# pcb.net
KiCad netlist of a schematic drawn in EAGLE
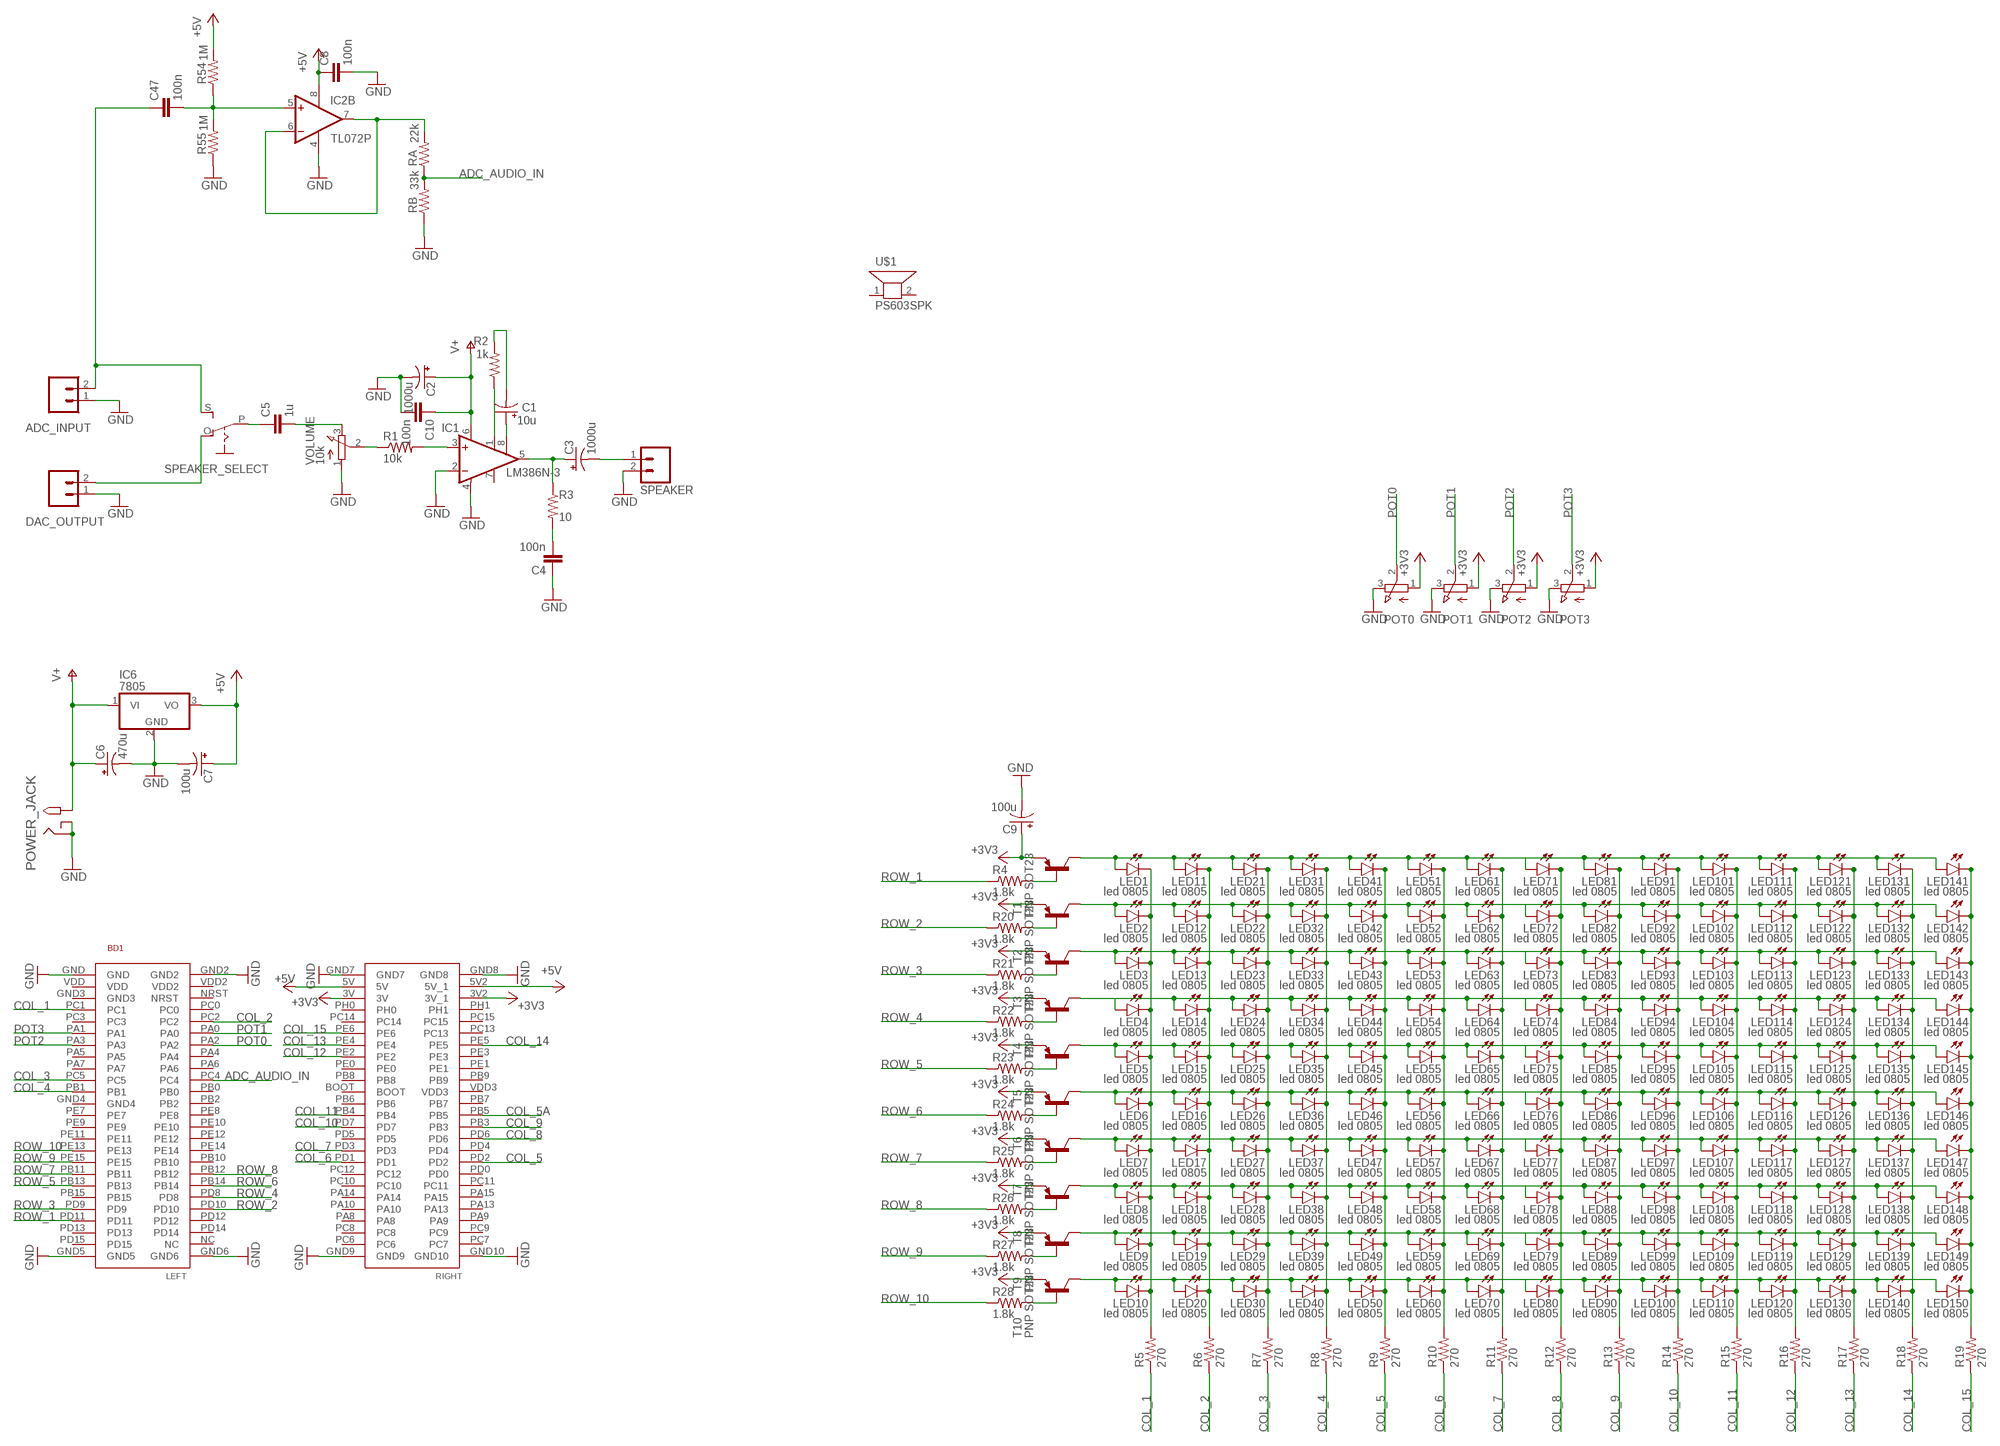
[diagram p0: schematic, sheet 1]

(export (version "E")
  (design (tool "Eeschema 10.0.6"))
  (components
    (comp (ref "ADC_INPUT")
      (value "M02")
      (footprint "eagle-import:02P")
      (libsource (lib "eagle-import") (part "M02"))
    )
    (comp (ref "BD1")
      (value "STM32F4-DISCOVERY")
      (footprint "eagle-import:STM32F407VG")
      (libsource (lib "eagle-import") (part "STM32F4-DISCOVERY"))
    )
    (comp (ref "C1")
      (value "10u")
      (footprint "eagle-import:E5-6")
      (libsource (lib "eagle-import") (part "CPOL-USE5-6"))
    )
    (comp (ref "C2")
      (value "1000u")
      (footprint "eagle-import:E5-13")
      (libsource (lib "eagle-import") (part "CPOL-USE5-13"))
    )
    (comp (ref "C3")
      (value "1000u")
      (footprint "eagle-import:E5-13")
      (libsource (lib "eagle-import") (part "CPOL-USE5-13"))
    )
    (comp (ref "C4")
      (value "100n")
      (footprint "eagle-import:C5B3.5")
      (libsource (lib "eagle-import") (part "C5/3.5"))
    )
    (comp (ref "C5")
      (value "1u")
      (footprint "eagle-import:C050-035X075")
      (libsource (lib "eagle-import") (part "rcl_334_C-EU050-035X075"))
    )
    (comp (ref "C6")
      (value "470u")
      (footprint "eagle-import:E5-6")
      (libsource (lib "eagle-import") (part "CPOL-USE5-6"))
    )
    (comp (ref "C7")
      (value "100u")
      (footprint "eagle-import:E5-6")
      (libsource (lib "eagle-import") (part "CPOL-USE5-6"))
    )
    (comp (ref "C8")
      (value "100n")
      (footprint "eagle-import:C0805")
      (libsource (lib "eagle-import") (part "C-EUC0805"))
    )
    (comp (ref "C9")
      (value "100u")
      (footprint "eagle-import:E5-6")
      (libsource (lib "eagle-import") (part "CPOL-USE5-6"))
    )
    (comp (ref "C10")
      (value "100n")
      (footprint "eagle-import:C0805")
      (libsource (lib "eagle-import") (part "C-EUC0805"))
    )
    (comp (ref "C47")
      (value "100n")
      (footprint "eagle-import:C5B3.5")
      (libsource (lib "eagle-import") (part "C5/3.5"))
    )
    (comp (ref "DAC_OUTPUT")
      (value "M02")
      (footprint "eagle-import:02P")
      (libsource (lib "eagle-import") (part "M02"))
    )
    (comp (ref "IC1")
      (value "LM386N-3")
      (footprint "eagle-import:DIL08")
      (libsource (lib "eagle-import") (part "LM386?-N3"))
    )
    (comp (ref "IC2")
      (value "TL072P")
      (footprint "eagle-import:DIL08")
      (libsource (lib "eagle-import") (part "TL072P"))
    )
    (comp (ref "IC6")
      (value "7805")
      (footprint "eagle-import:TO220H")
      (libsource (lib "eagle-import") (part "78T05"))
    )
    (comp (ref "LED1")
      (value "led 0805")
      (footprint "eagle-import:CHIPLED_0805")
      (libsource (lib "eagle-import") (part "LEDCHIPLED_0805"))
    )
    (comp (ref "LED2")
      (value "led 0805")
      (footprint "eagle-import:CHIPLED_0805")
      (libsource (lib "eagle-import") (part "LEDCHIPLED_0805"))
    )
    (comp (ref "LED3")
      (value "led 0805")
      (footprint "eagle-import:CHIPLED_0805")
      (libsource (lib "eagle-import") (part "LEDCHIPLED_0805"))
    )
    (comp (ref "LED4")
      (value "led 0805")
      (footprint "eagle-import:CHIPLED_0805")
      (libsource (lib "eagle-import") (part "LEDCHIPLED_0805"))
    )
    (comp (ref "LED5")
      (value "led 0805")
      (footprint "eagle-import:CHIPLED_0805")
      (libsource (lib "eagle-import") (part "LEDCHIPLED_0805"))
    )
    (comp (ref "LED6")
      (value "led 0805")
      (footprint "eagle-import:CHIPLED_0805")
      (libsource (lib "eagle-import") (part "LEDCHIPLED_0805"))
    )
    (comp (ref "LED7")
      (value "led 0805")
      (footprint "eagle-import:CHIPLED_0805")
      (libsource (lib "eagle-import") (part "LEDCHIPLED_0805"))
    )
    (comp (ref "LED8")
      (value "led 0805")
      (footprint "eagle-import:CHIPLED_0805")
      (libsource (lib "eagle-import") (part "LEDCHIPLED_0805"))
    )
    (comp (ref "LED9")
      (value "led 0805")
      (footprint "eagle-import:CHIPLED_0805")
      (libsource (lib "eagle-import") (part "LEDCHIPLED_0805"))
    )
    (comp (ref "LED10")
      (value "led 0805")
      (footprint "eagle-import:CHIPLED_0805")
      (libsource (lib "eagle-import") (part "LEDCHIPLED_0805"))
    )
    (comp (ref "LED11")
      (value "led 0805")
      (footprint "eagle-import:CHIPLED_0805")
      (libsource (lib "eagle-import") (part "LEDCHIPLED_0805"))
    )
    (comp (ref "LED12")
      (value "led 0805")
      (footprint "eagle-import:CHIPLED_0805")
      (libsource (lib "eagle-import") (part "LEDCHIPLED_0805"))
    )
    (comp (ref "LED13")
      (value "led 0805")
      (footprint "eagle-import:CHIPLED_0805")
      (libsource (lib "eagle-import") (part "LEDCHIPLED_0805"))
    )
    (comp (ref "LED14")
      (value "led 0805")
      (footprint "eagle-import:CHIPLED_0805")
      (libsource (lib "eagle-import") (part "LEDCHIPLED_0805"))
    )
    (comp (ref "LED15")
      (value "led 0805")
      (footprint "eagle-import:CHIPLED_0805")
      (libsource (lib "eagle-import") (part "LEDCHIPLED_0805"))
    )
    (comp (ref "LED16")
      (value "led 0805")
      (footprint "eagle-import:CHIPLED_0805")
      (libsource (lib "eagle-import") (part "LEDCHIPLED_0805"))
    )
    (comp (ref "LED17")
      (value "led 0805")
      (footprint "eagle-import:CHIPLED_0805")
      (libsource (lib "eagle-import") (part "LEDCHIPLED_0805"))
    )
    (comp (ref "LED18")
      (value "led 0805")
      (footprint "eagle-import:CHIPLED_0805")
      (libsource (lib "eagle-import") (part "LEDCHIPLED_0805"))
    )
    (comp (ref "LED19")
      (value "led 0805")
      (footprint "eagle-import:CHIPLED_0805")
      (libsource (lib "eagle-import") (part "LEDCHIPLED_0805"))
    )
    (comp (ref "LED20")
      (value "led 0805")
      (footprint "eagle-import:CHIPLED_0805")
      (libsource (lib "eagle-import") (part "LEDCHIPLED_0805"))
    )
    (comp (ref "LED21")
      (value "led 0805")
      (footprint "eagle-import:CHIPLED_0805")
      (libsource (lib "eagle-import") (part "LEDCHIPLED_0805"))
    )
    (comp (ref "LED22")
      (value "led 0805")
      (footprint "eagle-import:CHIPLED_0805")
      (libsource (lib "eagle-import") (part "LEDCHIPLED_0805"))
    )
    (comp (ref "LED23")
      (value "led 0805")
      (footprint "eagle-import:CHIPLED_0805")
      (libsource (lib "eagle-import") (part "LEDCHIPLED_0805"))
    )
    (comp (ref "LED24")
      (value "led 0805")
      (footprint "eagle-import:CHIPLED_0805")
      (libsource (lib "eagle-import") (part "LEDCHIPLED_0805"))
    )
    (comp (ref "LED25")
      (value "led 0805")
      (footprint "eagle-import:CHIPLED_0805")
      (libsource (lib "eagle-import") (part "LEDCHIPLED_0805"))
    )
    (comp (ref "LED26")
      (value "led 0805")
      (footprint "eagle-import:CHIPLED_0805")
      (libsource (lib "eagle-import") (part "LEDCHIPLED_0805"))
    )
    (comp (ref "LED27")
      (value "led 0805")
      (footprint "eagle-import:CHIPLED_0805")
      (libsource (lib "eagle-import") (part "LEDCHIPLED_0805"))
    )
    (comp (ref "LED28")
      (value "led 0805")
      (footprint "eagle-import:CHIPLED_0805")
      (libsource (lib "eagle-import") (part "LEDCHIPLED_0805"))
    )
    (comp (ref "LED29")
      (value "led 0805")
      (footprint "eagle-import:CHIPLED_0805")
      (libsource (lib "eagle-import") (part "LEDCHIPLED_0805"))
    )
    (comp (ref "LED30")
      (value "led 0805")
      (footprint "eagle-import:CHIPLED_0805")
      (libsource (lib "eagle-import") (part "LEDCHIPLED_0805"))
    )
    (comp (ref "LED31")
      (value "led 0805")
      (footprint "eagle-import:CHIPLED_0805")
      (libsource (lib "eagle-import") (part "LEDCHIPLED_0805"))
    )
    (comp (ref "LED32")
      (value "led 0805")
      (footprint "eagle-import:CHIPLED_0805")
      (libsource (lib "eagle-import") (part "LEDCHIPLED_0805"))
    )
    (comp (ref "LED33")
      (value "led 0805")
      (footprint "eagle-import:CHIPLED_0805")
      (libsource (lib "eagle-import") (part "LEDCHIPLED_0805"))
    )
    (comp (ref "LED34")
      (value "led 0805")
      (footprint "eagle-import:CHIPLED_0805")
      (libsource (lib "eagle-import") (part "LEDCHIPLED_0805"))
    )
    (comp (ref "LED35")
      (value "led 0805")
      (footprint "eagle-import:CHIPLED_0805")
      (libsource (lib "eagle-import") (part "LEDCHIPLED_0805"))
    )
    (comp (ref "LED36")
      (value "led 0805")
      (footprint "eagle-import:CHIPLED_0805")
      (libsource (lib "eagle-import") (part "LEDCHIPLED_0805"))
    )
    (comp (ref "LED37")
      (value "led 0805")
      (footprint "eagle-import:CHIPLED_0805")
      (libsource (lib "eagle-import") (part "LEDCHIPLED_0805"))
    )
    (comp (ref "LED38")
      (value "led 0805")
      (footprint "eagle-import:CHIPLED_0805")
      (libsource (lib "eagle-import") (part "LEDCHIPLED_0805"))
    )
    (comp (ref "LED39")
      (value "led 0805")
      (footprint "eagle-import:CHIPLED_0805")
      (libsource (lib "eagle-import") (part "LEDCHIPLED_0805"))
    )
    (comp (ref "LED40")
      (value "led 0805")
      (footprint "eagle-import:CHIPLED_0805")
      (libsource (lib "eagle-import") (part "LEDCHIPLED_0805"))
    )
    (comp (ref "LED41")
      (value "led 0805")
      (footprint "eagle-import:CHIPLED_0805")
      (libsource (lib "eagle-import") (part "LEDCHIPLED_0805"))
    )
    (comp (ref "LED42")
      (value "led 0805")
      (footprint "eagle-import:CHIPLED_0805")
      (libsource (lib "eagle-import") (part "LEDCHIPLED_0805"))
    )
    (comp (ref "LED43")
      (value "led 0805")
      (footprint "eagle-import:CHIPLED_0805")
      (libsource (lib "eagle-import") (part "LEDCHIPLED_0805"))
    )
    (comp (ref "LED44")
      (value "led 0805")
      (footprint "eagle-import:CHIPLED_0805")
      (libsource (lib "eagle-import") (part "LEDCHIPLED_0805"))
    )
    (comp (ref "LED45")
      (value "led 0805")
      (footprint "eagle-import:CHIPLED_0805")
      (libsource (lib "eagle-import") (part "LEDCHIPLED_0805"))
    )
    (comp (ref "LED46")
      (value "led 0805")
      (footprint "eagle-import:CHIPLED_0805")
      (libsource (lib "eagle-import") (part "LEDCHIPLED_0805"))
    )
    (comp (ref "LED47")
      (value "led 0805")
      (footprint "eagle-import:CHIPLED_0805")
      (libsource (lib "eagle-import") (part "LEDCHIPLED_0805"))
    )
    (comp (ref "LED48")
      (value "led 0805")
      (footprint "eagle-import:CHIPLED_0805")
      (libsource (lib "eagle-import") (part "LEDCHIPLED_0805"))
    )
    (comp (ref "LED49")
      (value "led 0805")
      (footprint "eagle-import:CHIPLED_0805")
      (libsource (lib "eagle-import") (part "LEDCHIPLED_0805"))
    )
    (comp (ref "LED50")
      (value "led 0805")
      (footprint "eagle-import:CHIPLED_0805")
      (libsource (lib "eagle-import") (part "LEDCHIPLED_0805"))
    )
    (comp (ref "LED51")
      (value "led 0805")
      (footprint "eagle-import:CHIPLED_0805")
      (libsource (lib "eagle-import") (part "LEDCHIPLED_0805"))
    )
    (comp (ref "LED52")
      (value "led 0805")
      (footprint "eagle-import:CHIPLED_0805")
      (libsource (lib "eagle-import") (part "LEDCHIPLED_0805"))
    )
    (comp (ref "LED53")
      (value "led 0805")
      (footprint "eagle-import:CHIPLED_0805")
      (libsource (lib "eagle-import") (part "LEDCHIPLED_0805"))
    )
    (comp (ref "LED54")
      (value "led 0805")
      (footprint "eagle-import:CHIPLED_0805")
      (libsource (lib "eagle-import") (part "LEDCHIPLED_0805"))
    )
    (comp (ref "LED55")
      (value "led 0805")
      (footprint "eagle-import:CHIPLED_0805")
      (libsource (lib "eagle-import") (part "LEDCHIPLED_0805"))
    )
    (comp (ref "LED56")
      (value "led 0805")
      (footprint "eagle-import:CHIPLED_0805")
      (libsource (lib "eagle-import") (part "LEDCHIPLED_0805"))
    )
    (comp (ref "LED57")
      (value "led 0805")
      (footprint "eagle-import:CHIPLED_0805")
      (libsource (lib "eagle-import") (part "LEDCHIPLED_0805"))
    )
    (comp (ref "LED58")
      (value "led 0805")
      (footprint "eagle-import:CHIPLED_0805")
      (libsource (lib "eagle-import") (part "LEDCHIPLED_0805"))
    )
    (comp (ref "LED59")
      (value "led 0805")
      (footprint "eagle-import:CHIPLED_0805")
      (libsource (lib "eagle-import") (part "LEDCHIPLED_0805"))
    )
    (comp (ref "LED60")
      (value "led 0805")
      (footprint "eagle-import:CHIPLED_0805")
      (libsource (lib "eagle-import") (part "LEDCHIPLED_0805"))
    )
    (comp (ref "LED61")
      (value "led 0805")
      (footprint "eagle-import:CHIPLED_0805")
      (libsource (lib "eagle-import") (part "LEDCHIPLED_0805"))
    )
    (comp (ref "LED62")
      (value "led 0805")
      (footprint "eagle-import:CHIPLED_0805")
      (libsource (lib "eagle-import") (part "LEDCHIPLED_0805"))
    )
    (comp (ref "LED63")
      (value "led 0805")
      (footprint "eagle-import:CHIPLED_0805")
      (libsource (lib "eagle-import") (part "LEDCHIPLED_0805"))
    )
    (comp (ref "LED64")
      (value "led 0805")
      (footprint "eagle-import:CHIPLED_0805")
      (libsource (lib "eagle-import") (part "LEDCHIPLED_0805"))
    )
    (comp (ref "LED65")
      (value "led 0805")
      (footprint "eagle-import:CHIPLED_0805")
      (libsource (lib "eagle-import") (part "LEDCHIPLED_0805"))
    )
    (comp (ref "LED66")
      (value "led 0805")
      (footprint "eagle-import:CHIPLED_0805")
      (libsource (lib "eagle-import") (part "LEDCHIPLED_0805"))
    )
    (comp (ref "LED67")
      (value "led 0805")
      (footprint "eagle-import:CHIPLED_0805")
      (libsource (lib "eagle-import") (part "LEDCHIPLED_0805"))
    )
    (comp (ref "LED68")
      (value "led 0805")
      (footprint "eagle-import:CHIPLED_0805")
      (libsource (lib "eagle-import") (part "LEDCHIPLED_0805"))
    )
    (comp (ref "LED69")
      (value "led 0805")
      (footprint "eagle-import:CHIPLED_0805")
      (libsource (lib "eagle-import") (part "LEDCHIPLED_0805"))
    )
    (comp (ref "LED70")
      (value "led 0805")
      (footprint "eagle-import:CHIPLED_0805")
      (libsource (lib "eagle-import") (part "LEDCHIPLED_0805"))
    )
    (comp (ref "LED71")
      (value "led 0805")
      (footprint "eagle-import:CHIPLED_0805")
      (libsource (lib "eagle-import") (part "LEDCHIPLED_0805"))
    )
    (comp (ref "LED72")
      (value "led 0805")
      (footprint "eagle-import:CHIPLED_0805")
      (libsource (lib "eagle-import") (part "LEDCHIPLED_0805"))
    )
    (comp (ref "LED73")
      (value "led 0805")
      (footprint "eagle-import:CHIPLED_0805")
      (libsource (lib "eagle-import") (part "LEDCHIPLED_0805"))
    )
    (comp (ref "LED74")
      (value "led 0805")
      (footprint "eagle-import:CHIPLED_0805")
      (libsource (lib "eagle-import") (part "LEDCHIPLED_0805"))
    )
    (comp (ref "LED75")
      (value "led 0805")
      (footprint "eagle-import:CHIPLED_0805")
      (libsource (lib "eagle-import") (part "LEDCHIPLED_0805"))
    )
    (comp (ref "LED76")
      (value "led 0805")
      (footprint "eagle-import:CHIPLED_0805")
      (libsource (lib "eagle-import") (part "LEDCHIPLED_0805"))
    )
    (comp (ref "LED77")
      (value "led 0805")
      (footprint "eagle-import:CHIPLED_0805")
      (libsource (lib "eagle-import") (part "LEDCHIPLED_0805"))
    )
    (comp (ref "LED78")
      (value "led 0805")
      (footprint "eagle-import:CHIPLED_0805")
      (libsource (lib "eagle-import") (part "LEDCHIPLED_0805"))
    )
    (comp (ref "LED79")
      (value "led 0805")
      (footprint "eagle-import:CHIPLED_0805")
      (libsource (lib "eagle-import") (part "LEDCHIPLED_0805"))
    )
    (comp (ref "LED80")
      (value "led 0805")
      (footprint "eagle-import:CHIPLED_0805")
      (libsource (lib "eagle-import") (part "LEDCHIPLED_0805"))
    )
    (comp (ref "LED81")
      (value "led 0805")
      (footprint "eagle-import:CHIPLED_0805")
      (libsource (lib "eagle-import") (part "LEDCHIPLED_0805"))
    )
    (comp (ref "LED82")
      (value "led 0805")
      (footprint "eagle-import:CHIPLED_0805")
      (libsource (lib "eagle-import") (part "LEDCHIPLED_0805"))
    )
    (comp (ref "LED83")
      (value "led 0805")
      (footprint "eagle-import:CHIPLED_0805")
      (libsource (lib "eagle-import") (part "LEDCHIPLED_0805"))
    )
    (comp (ref "LED84")
      (value "led 0805")
      (footprint "eagle-import:CHIPLED_0805")
      (libsource (lib "eagle-import") (part "LEDCHIPLED_0805"))
    )
    (comp (ref "LED85")
      (value "led 0805")
      (footprint "eagle-import:CHIPLED_0805")
      (libsource (lib "eagle-import") (part "LEDCHIPLED_0805"))
    )
    (comp (ref "LED86")
      (value "led 0805")
      (footprint "eagle-import:CHIPLED_0805")
      (libsource (lib "eagle-import") (part "LEDCHIPLED_0805"))
    )
    (comp (ref "LED87")
      (value "led 0805")
      (footprint "eagle-import:CHIPLED_0805")
      (libsource (lib "eagle-import") (part "LEDCHIPLED_0805"))
    )
    (comp (ref "LED88")
      (value "led 0805")
      (footprint "eagle-import:CHIPLED_0805")
      (libsource (lib "eagle-import") (part "LEDCHIPLED_0805"))
    )
    (comp (ref "LED89")
      (value "led 0805")
      (footprint "eagle-import:CHIPLED_0805")
      (libsource (lib "eagle-import") (part "LEDCHIPLED_0805"))
    )
    (comp (ref "LED90")
      (value "led 0805")
      (footprint "eagle-import:CHIPLED_0805")
      (libsource (lib "eagle-import") (part "LEDCHIPLED_0805"))
    )
    (comp (ref "LED91")
      (value "led 0805")
      (footprint "eagle-import:CHIPLED_0805")
      (libsource (lib "eagle-import") (part "LEDCHIPLED_0805"))
    )
    (comp (ref "LED92")
      (value "led 0805")
      (footprint "eagle-import:CHIPLED_0805")
      (libsource (lib "eagle-import") (part "LEDCHIPLED_0805"))
    )
    (comp (ref "LED93")
      (value "led 0805")
      (footprint "eagle-import:CHIPLED_0805")
      (libsource (lib "eagle-import") (part "LEDCHIPLED_0805"))
    )
    (comp (ref "LED94")
      (value "led 0805")
      (footprint "eagle-import:CHIPLED_0805")
      (libsource (lib "eagle-import") (part "LEDCHIPLED_0805"))
    )
    (comp (ref "LED95")
      (value "led 0805")
      (footprint "eagle-import:CHIPLED_0805")
      (libsource (lib "eagle-import") (part "LEDCHIPLED_0805"))
    )
    (comp (ref "LED96")
      (value "led 0805")
      (footprint "eagle-import:CHIPLED_0805")
      (libsource (lib "eagle-import") (part "LEDCHIPLED_0805"))
    )
    (comp (ref "LED97")
      (value "led 0805")
      (footprint "eagle-import:CHIPLED_0805")
      (libsource (lib "eagle-import") (part "LEDCHIPLED_0805"))
    )
    (comp (ref "LED98")
      (value "led 0805")
      (footprint "eagle-import:CHIPLED_0805")
      (libsource (lib "eagle-import") (part "LEDCHIPLED_0805"))
    )
    (comp (ref "LED99")
      (value "led 0805")
      (footprint "eagle-import:CHIPLED_0805")
      (libsource (lib "eagle-import") (part "LEDCHIPLED_0805"))
    )
    (comp (ref "LED100")
      (value "led 0805")
      (footprint "eagle-import:CHIPLED_0805")
      (libsource (lib "eagle-import") (part "LEDCHIPLED_0805"))
    )
    (comp (ref "LED101")
      (value "led 0805")
      (footprint "eagle-import:CHIPLED_0805")
      (libsource (lib "eagle-import") (part "LEDCHIPLED_0805"))
    )
    (comp (ref "LED102")
      (value "led 0805")
      (footprint "eagle-import:CHIPLED_0805")
      (libsource (lib "eagle-import") (part "LEDCHIPLED_0805"))
    )
    (comp (ref "LED103")
      (value "led 0805")
      (footprint "eagle-import:CHIPLED_0805")
      (libsource (lib "eagle-import") (part "LEDCHIPLED_0805"))
    )
    (comp (ref "LED104")
      (value "led 0805")
      (footprint "eagle-import:CHIPLED_0805")
      (libsource (lib "eagle-import") (part "LEDCHIPLED_0805"))
    )
    (comp (ref "LED105")
      (value "led 0805")
      (footprint "eagle-import:CHIPLED_0805")
      (libsource (lib "eagle-import") (part "LEDCHIPLED_0805"))
    )
    (comp (ref "LED106")
      (value "led 0805")
      (footprint "eagle-import:CHIPLED_0805")
      (libsource (lib "eagle-import") (part "LEDCHIPLED_0805"))
    )
    (comp (ref "LED107")
      (value "led 0805")
      (footprint "eagle-import:CHIPLED_0805")
      (libsource (lib "eagle-import") (part "LEDCHIPLED_0805"))
    )
    (comp (ref "LED108")
      (value "led 0805")
      (footprint "eagle-import:CHIPLED_0805")
      (libsource (lib "eagle-import") (part "LEDCHIPLED_0805"))
    )
    (comp (ref "LED109")
      (value "led 0805")
      (footprint "eagle-import:CHIPLED_0805")
      (libsource (lib "eagle-import") (part "LEDCHIPLED_0805"))
    )
    (comp (ref "LED110")
      (value "led 0805")
      (footprint "eagle-import:CHIPLED_0805")
      (libsource (lib "eagle-import") (part "LEDCHIPLED_0805"))
    )
    (comp (ref "LED111")
      (value "led 0805")
      (footprint "eagle-import:CHIPLED_0805")
      (libsource (lib "eagle-import") (part "LEDCHIPLED_0805"))
    )
    (comp (ref "LED112")
      (value "led 0805")
      (footprint "eagle-import:CHIPLED_0805")
      (libsource (lib "eagle-import") (part "LEDCHIPLED_0805"))
    )
    (comp (ref "LED113")
      (value "led 0805")
      (footprint "eagle-import:CHIPLED_0805")
      (libsource (lib "eagle-import") (part "LEDCHIPLED_0805"))
    )
    (comp (ref "LED114")
      (value "led 0805")
      (footprint "eagle-import:CHIPLED_0805")
      (libsource (lib "eagle-import") (part "LEDCHIPLED_0805"))
    )
    (comp (ref "LED115")
      (value "led 0805")
      (footprint "eagle-import:CHIPLED_0805")
      (libsource (lib "eagle-import") (part "LEDCHIPLED_0805"))
    )
    (comp (ref "LED116")
      (value "led 0805")
      (footprint "eagle-import:CHIPLED_0805")
      (libsource (lib "eagle-import") (part "LEDCHIPLED_0805"))
    )
    (comp (ref "LED117")
      (value "led 0805")
      (footprint "eagle-import:CHIPLED_0805")
      (libsource (lib "eagle-import") (part "LEDCHIPLED_0805"))
    )
    (comp (ref "LED118")
      (value "led 0805")
      (footprint "eagle-import:CHIPLED_0805")
      (libsource (lib "eagle-import") (part "LEDCHIPLED_0805"))
    )
    (comp (ref "LED119")
      (value "led 0805")
      (footprint "eagle-import:CHIPLED_0805")
      (libsource (lib "eagle-import") (part "LEDCHIPLED_0805"))
    )
    (comp (ref "LED120")
      (value "led 0805")
      (footprint "eagle-import:CHIPLED_0805")
      (libsource (lib "eagle-import") (part "LEDCHIPLED_0805"))
    )
    (comp (ref "LED121")
      (value "led 0805")
      (footprint "eagle-import:CHIPLED_0805")
      (libsource (lib "eagle-import") (part "LEDCHIPLED_0805"))
    )
    (comp (ref "LED122")
      (value "led 0805")
      (footprint "eagle-import:CHIPLED_0805")
      (libsource (lib "eagle-import") (part "LEDCHIPLED_0805"))
    )
    (comp (ref "LED123")
      (value "led 0805")
      (footprint "eagle-import:CHIPLED_0805")
      (libsource (lib "eagle-import") (part "LEDCHIPLED_0805"))
    )
    (comp (ref "LED124")
      (value "led 0805")
      (footprint "eagle-import:CHIPLED_0805")
      (libsource (lib "eagle-import") (part "LEDCHIPLED_0805"))
    )
    (comp (ref "LED125")
      (value "led 0805")
      (footprint "eagle-import:CHIPLED_0805")
      (libsource (lib "eagle-import") (part "LEDCHIPLED_0805"))
    )
    (comp (ref "LED126")
      (value "led 0805")
      (footprint "eagle-import:CHIPLED_0805")
      (libsource (lib "eagle-import") (part "LEDCHIPLED_0805"))
    )
    (comp (ref "LED127")
      (value "led 0805")
      (footprint "eagle-import:CHIPLED_0805")
      (libsource (lib "eagle-import") (part "LEDCHIPLED_0805"))
    )
    (comp (ref "LED128")
      (value "led 0805")
      (footprint "eagle-import:CHIPLED_0805")
      (libsource (lib "eagle-import") (part "LEDCHIPLED_0805"))
    )
    (comp (ref "LED129")
      (value "led 0805")
      (footprint "eagle-import:CHIPLED_0805")
      (libsource (lib "eagle-import") (part "LEDCHIPLED_0805"))
    )
    (comp (ref "LED130")
      (value "led 0805")
      (footprint "eagle-import:CHIPLED_0805")
      (libsource (lib "eagle-import") (part "LEDCHIPLED_0805"))
    )
    (comp (ref "LED131")
      (value "led 0805")
      (footprint "eagle-import:CHIPLED_0805")
      (libsource (lib "eagle-import") (part "LEDCHIPLED_0805"))
    )
    (comp (ref "LED132")
      (value "led 0805")
      (footprint "eagle-import:CHIPLED_0805")
      (libsource (lib "eagle-import") (part "LEDCHIPLED_0805"))
    )
    (comp (ref "LED133")
      (value "led 0805")
      (footprint "eagle-import:CHIPLED_0805")
      (libsource (lib "eagle-import") (part "LEDCHIPLED_0805"))
    )
    (comp (ref "LED134")
      (value "led 0805")
      (footprint "eagle-import:CHIPLED_0805")
      (libsource (lib "eagle-import") (part "LEDCHIPLED_0805"))
    )
    (comp (ref "LED135")
      (value "led 0805")
      (footprint "eagle-import:CHIPLED_0805")
      (libsource (lib "eagle-import") (part "LEDCHIPLED_0805"))
    )
    (comp (ref "LED136")
      (value "led 0805")
      (footprint "eagle-import:CHIPLED_0805")
      (libsource (lib "eagle-import") (part "LEDCHIPLED_0805"))
    )
    (comp (ref "LED137")
      (value "led 0805")
      (footprint "eagle-import:CHIPLED_0805")
      (libsource (lib "eagle-import") (part "LEDCHIPLED_0805"))
    )
    (comp (ref "LED138")
      (value "led 0805")
      (footprint "eagle-import:CHIPLED_0805")
      (libsource (lib "eagle-import") (part "LEDCHIPLED_0805"))
    )
    (comp (ref "LED139")
      (value "led 0805")
      (footprint "eagle-import:CHIPLED_0805")
      (libsource (lib "eagle-import") (part "LEDCHIPLED_0805"))
    )
    (comp (ref "LED140")
      (value "led 0805")
      (footprint "eagle-import:CHIPLED_0805")
      (libsource (lib "eagle-import") (part "LEDCHIPLED_0805"))
    )
    (comp (ref "LED141")
      (value "led 0805")
      (footprint "eagle-import:CHIPLED_0805")
      (libsource (lib "eagle-import") (part "LEDCHIPLED_0805"))
    )
    (comp (ref "LED142")
      (value "led 0805")
      (footprint "eagle-import:CHIPLED_0805")
      (libsource (lib "eagle-import") (part "LEDCHIPLED_0805"))
    )
    (comp (ref "LED143")
      (value "led 0805")
      (footprint "eagle-import:CHIPLED_0805")
      (libsource (lib "eagle-import") (part "LEDCHIPLED_0805"))
    )
    (comp (ref "LED144")
      (value "led 0805")
      (footprint "eagle-import:CHIPLED_0805")
      (libsource (lib "eagle-import") (part "LEDCHIPLED_0805"))
    )
    (comp (ref "LED145")
      (value "led 0805")
      (footprint "eagle-import:CHIPLED_0805")
      (libsource (lib "eagle-import") (part "LEDCHIPLED_0805"))
    )
    (comp (ref "LED146")
      (value "led 0805")
      (footprint "eagle-import:CHIPLED_0805")
      (libsource (lib "eagle-import") (part "LEDCHIPLED_0805"))
    )
    (comp (ref "LED147")
      (value "led 0805")
      (footprint "eagle-import:CHIPLED_0805")
      (libsource (lib "eagle-import") (part "LEDCHIPLED_0805"))
    )
    (comp (ref "LED148")
      (value "led 0805")
      (footprint "eagle-import:CHIPLED_0805")
      (libsource (lib "eagle-import") (part "LEDCHIPLED_0805"))
    )
    (comp (ref "LED149")
      (value "led 0805")
      (footprint "eagle-import:CHIPLED_0805")
      (libsource (lib "eagle-import") (part "LEDCHIPLED_0805"))
    )
    (comp (ref "LED150")
      (value "led 0805")
      (footprint "eagle-import:CHIPLED_0805")
      (libsource (lib "eagle-import") (part "LEDCHIPLED_0805"))
    )
    (comp (ref "POT0")
      (value "3RP/1610N")
      (footprint "eagle-import:3RP_1610N")
      (libsource (lib "eagle-import") (part "3RP/1610N"))
    )
    (comp (ref "POT1")
      (value "3RP/1610N")
      (footprint "eagle-import:3RP_1610N")
      (libsource (lib "eagle-import") (part "3RP/1610N"))
    )
    (comp (ref "POT2")
      (value "3RP/1610N")
      (footprint "eagle-import:3RP_1610N")
      (libsource (lib "eagle-import") (part "3RP/1610N"))
    )
    (comp (ref "POT3")
      (value "3RP/1610N")
      (footprint "eagle-import:3RP_1610N")
      (libsource (lib "eagle-import") (part "3RP/1610N"))
    )
    (comp (ref "POWER_JACK")
      (value "2.1MMJACKTHM")
      (footprint "eagle-import:PJ-102A")
      (libsource (lib "eagle-import") (part "2.1MMJACKTHM"))
    )
    (comp (ref "R1")
      (value "10k")
      (footprint "eagle-import:0207_10")
      (libsource (lib "eagle-import") (part "R-US_0207/10"))
    )
    (comp (ref "R2")
      (value "1k")
      (footprint "eagle-import:0207_10")
      (libsource (lib "eagle-import") (part "R-US_0207/10"))
    )
    (comp (ref "R3")
      (value "10")
      (footprint "eagle-import:0207_10")
      (libsource (lib "eagle-import") (part "R-US_0207/10"))
    )
    (comp (ref "R4")
      (value "1.8k")
      (footprint "eagle-import:R0805")
      (libsource (lib "eagle-import") (part "rcl_334_R-US_R0805"))
    )
    (comp (ref "R5")
      (value "270")
      (footprint "eagle-import:R0805")
      (libsource (lib "eagle-import") (part "rcl_334_R-US_R0805"))
    )
    (comp (ref "R6")
      (value "270")
      (footprint "eagle-import:R0805")
      (libsource (lib "eagle-import") (part "rcl_334_R-US_R0805"))
    )
    (comp (ref "R7")
      (value "270")
      (footprint "eagle-import:R0805")
      (libsource (lib "eagle-import") (part "rcl_334_R-US_R0805"))
    )
    (comp (ref "R8")
      (value "270")
      (footprint "eagle-import:R0805")
      (libsource (lib "eagle-import") (part "rcl_334_R-US_R0805"))
    )
    (comp (ref "R9")
      (value "270")
      (footprint "eagle-import:R0805")
      (libsource (lib "eagle-import") (part "rcl_334_R-US_R0805"))
    )
    (comp (ref "R10")
      (value "270")
      (footprint "eagle-import:R0805")
      (libsource (lib "eagle-import") (part "rcl_334_R-US_R0805"))
    )
    (comp (ref "R11")
      (value "270")
      (footprint "eagle-import:R0805")
      (libsource (lib "eagle-import") (part "rcl_334_R-US_R0805"))
    )
    (comp (ref "R12")
      (value "270")
      (footprint "eagle-import:R0805")
      (libsource (lib "eagle-import") (part "rcl_334_R-US_R0805"))
    )
    (comp (ref "R13")
      (value "270")
      (footprint "eagle-import:R0805")
      (libsource (lib "eagle-import") (part "rcl_334_R-US_R0805"))
    )
    (comp (ref "R14")
      (value "270")
      (footprint "eagle-import:R0805")
      (libsource (lib "eagle-import") (part "rcl_334_R-US_R0805"))
    )
    (comp (ref "R15")
      (value "270")
      (footprint "eagle-import:R0805")
      (libsource (lib "eagle-import") (part "rcl_334_R-US_R0805"))
    )
    (comp (ref "R16")
      (value "270")
      (footprint "eagle-import:R0805")
      (libsource (lib "eagle-import") (part "rcl_334_R-US_R0805"))
    )
    (comp (ref "R17")
      (value "270")
      (footprint "eagle-import:R0805")
      (libsource (lib "eagle-import") (part "rcl_334_R-US_R0805"))
    )
    (comp (ref "R18")
      (value "270")
      (footprint "eagle-import:R0805")
      (libsource (lib "eagle-import") (part "rcl_334_R-US_R0805"))
    )
    (comp (ref "R19")
      (value "270")
      (footprint "eagle-import:R0805")
      (libsource (lib "eagle-import") (part "rcl_334_R-US_R0805"))
    )
    (comp (ref "R20")
      (value "1.8k")
      (footprint "eagle-import:R0805")
      (libsource (lib "eagle-import") (part "rcl_334_R-US_R0805"))
    )
    (comp (ref "R21")
      (value "1.8k")
      (footprint "eagle-import:R0805")
      (libsource (lib "eagle-import") (part "rcl_334_R-US_R0805"))
    )
    (comp (ref "R22")
      (value "1.8k")
      (footprint "eagle-import:R0805")
      (libsource (lib "eagle-import") (part "rcl_334_R-US_R0805"))
    )
    (comp (ref "R23")
      (value "1.8k")
      (footprint "eagle-import:R0805")
      (libsource (lib "eagle-import") (part "rcl_334_R-US_R0805"))
    )
    (comp (ref "R24")
      (value "1.8k")
      (footprint "eagle-import:R0805")
      (libsource (lib "eagle-import") (part "rcl_334_R-US_R0805"))
    )
    (comp (ref "R25")
      (value "1.8k")
      (footprint "eagle-import:R0805")
      (libsource (lib "eagle-import") (part "rcl_334_R-US_R0805"))
    )
    (comp (ref "R26")
      (value "1.8k")
      (footprint "eagle-import:R0805")
      (libsource (lib "eagle-import") (part "rcl_334_R-US_R0805"))
    )
    (comp (ref "R27")
      (value "1.8k")
      (footprint "eagle-import:R0805")
      (libsource (lib "eagle-import") (part "rcl_334_R-US_R0805"))
    )
    (comp (ref "R28")
      (value "1.8k")
      (footprint "eagle-import:R0805")
      (libsource (lib "eagle-import") (part "rcl_334_R-US_R0805"))
    )
    (comp (ref "R54")
      (value "1M")
      (footprint "eagle-import:0207_10")
      (libsource (lib "eagle-import") (part "R-US_0207/10"))
    )
    (comp (ref "R55")
      (value "1M")
      (footprint "eagle-import:0207_10")
      (libsource (lib "eagle-import") (part "R-US_0207/10"))
    )
    (comp (ref "RA")
      (value "22k")
      (footprint "eagle-import:0207_10")
      (libsource (lib "eagle-import") (part "R-US_0207/10"))
    )
    (comp (ref "RB")
      (value "33k")
      (footprint "eagle-import:0207_10")
      (libsource (lib "eagle-import") (part "R-US_0207/10"))
    )
    (comp (ref "SPEAKER")
      (value "M02")
      (footprint "eagle-import:02P")
      (libsource (lib "eagle-import") (part "M02"))
    )
    (comp (ref "SPEAKER_SELECT")
      (value "EG1218S")
      (footprint "eagle-import:EG1218")
      (libsource (lib "eagle-import") (part "EG1218S"))
    )
    (comp (ref "T1")
      (value "PNP SOT23")
      (footprint "eagle-import:SOT23-BEC")
      (libsource (lib "eagle-import") (part "-PNP-SOT23-BECBC856BLT1"))
    )
    (comp (ref "T2")
      (value "PNP SOT23")
      (footprint "eagle-import:SOT23-BEC")
      (libsource (lib "eagle-import") (part "-PNP-SOT23-BECBC856BLT1"))
    )
    (comp (ref "T3")
      (value "PNP SOT23")
      (footprint "eagle-import:SOT23-BEC")
      (libsource (lib "eagle-import") (part "-PNP-SOT23-BECBC856BLT1"))
    )
    (comp (ref "T4")
      (value "PNP SOT23")
      (footprint "eagle-import:SOT23-BEC")
      (libsource (lib "eagle-import") (part "-PNP-SOT23-BECBC856BLT1"))
    )
    (comp (ref "T5")
      (value "PNP SOT23")
      (footprint "eagle-import:SOT23-BEC")
      (libsource (lib "eagle-import") (part "-PNP-SOT23-BECBC856BLT1"))
    )
    (comp (ref "T6")
      (value "PNP SOT23")
      (footprint "eagle-import:SOT23-BEC")
      (libsource (lib "eagle-import") (part "-PNP-SOT23-BECBC856BLT1"))
    )
    (comp (ref "T7")
      (value "PNP SOT23")
      (footprint "eagle-import:SOT23-BEC")
      (libsource (lib "eagle-import") (part "-PNP-SOT23-BECBC856BLT1"))
    )
    (comp (ref "T8")
      (value "PNP SOT23")
      (footprint "eagle-import:SOT23-BEC")
      (libsource (lib "eagle-import") (part "-PNP-SOT23-BECBC856BLT1"))
    )
    (comp (ref "T9")
      (value "PNP SOT23")
      (footprint "eagle-import:SOT23-BEC")
      (libsource (lib "eagle-import") (part "-PNP-SOT23-BECBC856BLT1"))
    )
    (comp (ref "T10")
      (value "PNP SOT23")
      (footprint "eagle-import:SOT23-BEC")
      (libsource (lib "eagle-import") (part "-PNP-SOT23-BECBC856BLT1"))
    )
    (comp (ref "U$1")
      (value "PS603SPK")
      (footprint "eagle-import:PS603")
      (libsource (lib "eagle-import") (part "PS603SPK"))
    )
    (comp (ref "VOLUME")
      (value "10k")
      (footprint "eagle-import:3RP_1610N")
      (libsource (lib "eagle-import") (part "3RP/1610N"))
    )
  )
  (nets
    (net (code "1") (name "+3V3") (class "Default")
      (node (ref "BD1") (pin "3V") (pinfunction "3V_3V") (pintype "bidirectional"))
      (node (ref "BD1") (pin "3V2") (pinfunction "3V_1_3V2") (pintype "bidirectional"))
      (node (ref "C9") (pin "+") (pinfunction "+_+") (pintype "passive"))
      (node (ref "POT0") (pin "1") (pinfunction "A_1") (pintype "passive"))
      (node (ref "POT1") (pin "1") (pinfunction "A_1") (pintype "passive"))
      (node (ref "POT2") (pin "1") (pinfunction "A_1") (pintype "passive"))
      (node (ref "POT3") (pin "1") (pinfunction "A_1") (pintype "passive"))
      (node (ref "T1") (pin "E") (pinfunction "E_E") (pintype "passive"))
      (node (ref "T10") (pin "E") (pinfunction "E_E") (pintype "passive"))
      (node (ref "T2") (pin "E") (pinfunction "E_E") (pintype "passive"))
      (node (ref "T3") (pin "E") (pinfunction "E_E") (pintype "passive"))
      (node (ref "T4") (pin "E") (pinfunction "E_E") (pintype "passive"))
      (node (ref "T5") (pin "E") (pinfunction "E_E") (pintype "passive"))
      (node (ref "T6") (pin "E") (pinfunction "E_E") (pintype "passive"))
      (node (ref "T7") (pin "E") (pinfunction "E_E") (pintype "passive"))
      (node (ref "T8") (pin "E") (pinfunction "E_E") (pintype "passive"))
      (node (ref "T9") (pin "E") (pinfunction "E_E") (pintype "passive"))
    )
    (net (code "2") (name "+5V") (class "Default")
      (node (ref "BD1") (pin "5V") (pinfunction "5V_5V") (pintype "bidirectional"))
      (node (ref "BD1") (pin "5V2") (pinfunction "5V_1_5V2") (pintype "bidirectional"))
      (node (ref "C7") (pin "+") (pinfunction "+_+") (pintype "passive"))
      (node (ref "C8") (pin "1") (pinfunction "1_1") (pintype "passive"))
      (node (ref "IC2") (pin "8") (pinfunction "V+_8") (pintype "power_in"))
      (node (ref "IC6") (pin "3") (pinfunction "VO_3") (pintype "passive"))
      (node (ref "R54") (pin "2") (pinfunction "2_2") (pintype "passive"))
    )
    (net (code "3") (name "/ADC_AUDIO_IN") (class "Default")
      (node (ref "BD1") (pin "PC4") (pinfunction "PC4_PC4") (pintype "bidirectional"))
      (node (ref "RA") (pin "1") (pinfunction "1_1") (pintype "passive"))
      (node (ref "RB") (pin "2") (pinfunction "2_2") (pintype "passive"))
    )
    (net (code "4") (name "/COL_1") (class "Default")
      (node (ref "BD1") (pin "PC1") (pinfunction "PC1_PC1") (pintype "bidirectional"))
      (node (ref "R5") (pin "1") (pinfunction "1_1") (pintype "passive"))
    )
    (net (code "5") (name "/COL_2") (class "Default")
      (node (ref "BD1") (pin "PC2") (pinfunction "PC2_PC2") (pintype "bidirectional"))
      (node (ref "R6") (pin "1") (pinfunction "1_1") (pintype "passive"))
    )
    (net (code "6") (name "/COL_3") (class "Default")
      (node (ref "BD1") (pin "PC5") (pinfunction "PC5_PC5") (pintype "bidirectional"))
      (node (ref "R7") (pin "1") (pinfunction "1_1") (pintype "passive"))
    )
    (net (code "7") (name "/COL_4") (class "Default")
      (node (ref "BD1") (pin "PB1") (pinfunction "PB1_PB1") (pintype "bidirectional"))
      (node (ref "R8") (pin "1") (pinfunction "1_1") (pintype "passive"))
    )
    (net (code "8") (name "/COL_5") (class "Default")
      (node (ref "BD1") (pin "PD2") (pinfunction "PD2_PD2") (pintype "bidirectional"))
      (node (ref "R9") (pin "1") (pinfunction "1_1") (pintype "passive"))
    )
    (net (code "9") (name "/COL_5A") (class "Default")
      (node (ref "BD1") (pin "PB5") (pinfunction "PB5_PB5") (pintype "bidirectional"))
    )
    (net (code "10") (name "/COL_6") (class "Default")
      (node (ref "BD1") (pin "PD1") (pinfunction "PD1_PD1") (pintype "bidirectional"))
      (node (ref "R10") (pin "1") (pinfunction "1_1") (pintype "passive"))
    )
    (net (code "11") (name "/COL_7") (class "Default")
      (node (ref "BD1") (pin "PD3") (pinfunction "PD3_PD3") (pintype "bidirectional"))
      (node (ref "R11") (pin "1") (pinfunction "1_1") (pintype "passive"))
    )
    (net (code "12") (name "/COL_8") (class "Default")
      (node (ref "BD1") (pin "PD6") (pinfunction "PD6_PD6") (pintype "bidirectional"))
      (node (ref "R12") (pin "1") (pinfunction "1_1") (pintype "passive"))
    )
    (net (code "13") (name "/COL_9") (class "Default")
      (node (ref "BD1") (pin "PB3") (pinfunction "PB3_PB3") (pintype "bidirectional"))
      (node (ref "R13") (pin "1") (pinfunction "1_1") (pintype "passive"))
    )
    (net (code "14") (name "/COL_10") (class "Default")
      (node (ref "BD1") (pin "PD7") (pinfunction "PD7_PD7") (pintype "bidirectional"))
      (node (ref "R14") (pin "1") (pinfunction "1_1") (pintype "passive"))
    )
    (net (code "15") (name "/COL_11") (class "Default")
      (node (ref "BD1") (pin "PB4") (pinfunction "PB4_PB4") (pintype "bidirectional"))
      (node (ref "R15") (pin "1") (pinfunction "1_1") (pintype "passive"))
    )
    (net (code "16") (name "/COL_12") (class "Default")
      (node (ref "BD1") (pin "PE2") (pinfunction "PE2_PE2") (pintype "bidirectional"))
      (node (ref "R16") (pin "1") (pinfunction "1_1") (pintype "passive"))
    )
    (net (code "17") (name "/COL_13") (class "Default")
      (node (ref "BD1") (pin "PE4") (pinfunction "PE4_PE4") (pintype "bidirectional"))
      (node (ref "R17") (pin "1") (pinfunction "1_1") (pintype "passive"))
    )
    (net (code "18") (name "/COL_14") (class "Default")
      (node (ref "BD1") (pin "PE5") (pinfunction "PE5_PE5") (pintype "bidirectional"))
      (node (ref "R18") (pin "1") (pinfunction "1_1") (pintype "passive"))
    )
    (net (code "19") (name "/COL_15") (class "Default")
      (node (ref "BD1") (pin "PE6") (pinfunction "PE6_PE6") (pintype "bidirectional"))
      (node (ref "R19") (pin "1") (pinfunction "1_1") (pintype "passive"))
    )
    (net (code "20") (name "/POT0") (class "Default")
      (node (ref "BD1") (pin "PA2") (pinfunction "PA2_PA2") (pintype "bidirectional"))
      (node (ref "POT0") (pin "2") (pinfunction "S_2") (pintype "passive"))
    )
    (net (code "21") (name "/POT1") (class "Default")
      (node (ref "BD1") (pin "PA0") (pinfunction "PA0_PA0") (pintype "bidirectional"))
      (node (ref "POT1") (pin "2") (pinfunction "S_2") (pintype "passive"))
    )
    (net (code "22") (name "/POT2") (class "Default")
      (node (ref "BD1") (pin "PA3") (pinfunction "PA3_PA3") (pintype "bidirectional"))
      (node (ref "POT2") (pin "2") (pinfunction "S_2") (pintype "passive"))
    )
    (net (code "23") (name "/POT3") (class "Default")
      (node (ref "BD1") (pin "PA1") (pinfunction "PA1_PA1") (pintype "bidirectional"))
      (node (ref "POT3") (pin "2") (pinfunction "S_2") (pintype "passive"))
    )
    (net (code "24") (name "/ROW_1") (class "Default")
      (node (ref "BD1") (pin "PD11") (pinfunction "PD11_PD11") (pintype "bidirectional"))
      (node (ref "R4") (pin "1") (pinfunction "1_1") (pintype "passive"))
    )
    (net (code "25") (name "/ROW_2") (class "Default")
      (node (ref "BD1") (pin "PD10") (pinfunction "PD10_PD10") (pintype "bidirectional"))
      (node (ref "R20") (pin "1") (pinfunction "1_1") (pintype "passive"))
    )
    (net (code "26") (name "/ROW_3") (class "Default")
      (node (ref "BD1") (pin "PD9") (pinfunction "PD9_PD9") (pintype "bidirectional"))
      (node (ref "R21") (pin "1") (pinfunction "1_1") (pintype "passive"))
    )
    (net (code "27") (name "/ROW_4") (class "Default")
      (node (ref "BD1") (pin "PD8") (pinfunction "PD8_PD8") (pintype "bidirectional"))
      (node (ref "R22") (pin "1") (pinfunction "1_1") (pintype "passive"))
    )
    (net (code "28") (name "/ROW_5") (class "Default")
      (node (ref "BD1") (pin "PB13") (pinfunction "PB13_PB13") (pintype "bidirectional"))
      (node (ref "R23") (pin "1") (pinfunction "1_1") (pintype "passive"))
    )
    (net (code "29") (name "/ROW_6") (class "Default")
      (node (ref "BD1") (pin "PB14") (pinfunction "PB14_PB14") (pintype "bidirectional"))
      (node (ref "R24") (pin "1") (pinfunction "1_1") (pintype "passive"))
    )
    (net (code "30") (name "/ROW_7") (class "Default")
      (node (ref "BD1") (pin "PB11") (pinfunction "PB11_PB11") (pintype "bidirectional"))
      (node (ref "R25") (pin "1") (pinfunction "1_1") (pintype "passive"))
    )
    (net (code "31") (name "/ROW_8") (class "Default")
      (node (ref "BD1") (pin "PB12") (pinfunction "PB12_PB12") (pintype "bidirectional"))
      (node (ref "R26") (pin "1") (pinfunction "1_1") (pintype "passive"))
    )
    (net (code "32") (name "/ROW_9") (class "Default")
      (node (ref "BD1") (pin "PE15") (pinfunction "PE15_PE15") (pintype "bidirectional"))
      (node (ref "R27") (pin "1") (pinfunction "1_1") (pintype "passive"))
    )
    (net (code "33") (name "/ROW_10") (class "Default")
      (node (ref "BD1") (pin "PE13") (pinfunction "PE13_PE13") (pintype "bidirectional"))
      (node (ref "R28") (pin "1") (pinfunction "1_1") (pintype "passive"))
    )
    (net (code "34") (name "GND") (class "Default")
      (node (ref "ADC_INPUT") (pin "1") (pinfunction "1_1") (pintype "passive"))
      (node (ref "BD1") (pin "GND") (pinfunction "GND_GND") (pintype "bidirectional"))
      (node (ref "BD1") (pin "GND10") (pinfunction "GND10_GND10") (pintype "bidirectional"))
      (node (ref "BD1") (pin "GND2") (pinfunction "GND2_GND2") (pintype "bidirectional"))
      (node (ref "BD1") (pin "GND5") (pinfunction "GND5_GND5") (pintype "bidirectional"))
      (node (ref "BD1") (pin "GND6") (pinfunction "GND6_GND6") (pintype "bidirectional"))
      (node (ref "BD1") (pin "GND7") (pinfunction "GND7_GND7") (pintype "bidirectional"))
      (node (ref "BD1") (pin "GND8") (pinfunction "GND8_GND8") (pintype "bidirectional"))
      (node (ref "BD1") (pin "GND9") (pinfunction "GND9_GND9") (pintype "bidirectional"))
      (node (ref "C10") (pin "2") (pinfunction "2_2") (pintype "passive"))
      (node (ref "C2") (pin "-") (pinfunction "-_-") (pintype "passive"))
      (node (ref "C4") (pin "1") (pinfunction "1_1") (pintype "passive"))
      (node (ref "C6") (pin "-") (pinfunction "-_-") (pintype "passive"))
      (node (ref "C7") (pin "-") (pinfunction "-_-") (pintype "passive"))
      (node (ref "C8") (pin "2") (pinfunction "2_2") (pintype "passive"))
      (node (ref "C9") (pin "-") (pinfunction "-_-") (pintype "passive"))
      (node (ref "DAC_OUTPUT") (pin "1") (pinfunction "1_1") (pintype "passive"))
      (node (ref "IC1") (pin "2") (pinfunction "-IN_2") (pintype "input"))
      (node (ref "IC1") (pin "4") (pinfunction "GND_4") (pintype "power_in"))
      (node (ref "IC2") (pin "4") (pinfunction "V-_4") (pintype "power_in"))
      (node (ref "IC6") (pin "2") (pinfunction "GND_2") (pintype "passive"))
      (node (ref "POT0") (pin "3") (pinfunction "E_3") (pintype "passive"))
      (node (ref "POT1") (pin "3") (pinfunction "E_3") (pintype "passive"))
      (node (ref "POT2") (pin "3") (pinfunction "E_3") (pintype "passive"))
      (node (ref "POT3") (pin "3") (pinfunction "E_3") (pintype "passive"))
      (node (ref "POWER_JACK") (pin "RING") (pinfunction "RING_RING") (pintype "bidirectional"))
      (node (ref "POWER_JACK") (pin "RING_SW") (pinfunction "RING_SW_RING_SW") (pintype "bidirectional"))
      (node (ref "R55") (pin "1") (pinfunction "1_1") (pintype "passive"))
      (node (ref "RB") (pin "1") (pinfunction "1_1") (pintype "passive"))
      (node (ref "SPEAKER") (pin "2") (pinfunction "2_2") (pintype "passive"))
      (node (ref "VOLUME") (pin "1") (pinfunction "A_1") (pintype "passive"))
    )
    (net (code "35") (name "Net-(ADC_INPUT-Pad2)") (class "Default")
      (node (ref "ADC_INPUT") (pin "2") (pinfunction "2_2") (pintype "passive"))
      (node (ref "C47") (pin "1") (pinfunction "1_1") (pintype "passive"))
      (node (ref "SPEAKER_SELECT") (pin "S") (pinfunction "S_S") (pintype "passive"))
    )
    (net (code "36") (name "Net-(C1-Pad+)") (class "Default")
      (node (ref "C1") (pin "+") (pinfunction "+_+") (pintype "passive"))
      (node (ref "IC1") (pin "8") (pinfunction "GAIN_8") (pintype "passive"))
    )
    (net (code "37") (name "Net-(C1-Pad-)") (class "Default")
      (node (ref "C1") (pin "-") (pinfunction "-_-") (pintype "passive"))
      (node (ref "R2") (pin "2") (pinfunction "2_2") (pintype "passive"))
    )
    (net (code "38") (name "Net-(C3-Pad-)") (class "Default")
      (node (ref "C3") (pin "-") (pinfunction "-_-") (pintype "passive"))
      (node (ref "SPEAKER") (pin "1") (pinfunction "1_1") (pintype "passive"))
    )
    (net (code "39") (name "Net-(C4-Pad2)") (class "Default")
      (node (ref "C4") (pin "2") (pinfunction "2_2") (pintype "passive"))
      (node (ref "R3") (pin "2") (pinfunction "2_2") (pintype "passive"))
    )
    (net (code "40") (name "Net-(C5-Pad1)") (class "Default")
      (node (ref "C5") (pin "1") (pinfunction "1_1") (pintype "passive"))
      (node (ref "SPEAKER_SELECT") (pin "P") (pinfunction "P_P") (pintype "passive"))
    )
    (net (code "41") (name "Net-(DAC_OUTPUT-Pad2)") (class "Default")
      (node (ref "DAC_OUTPUT") (pin "2") (pinfunction "2_2") (pintype "passive"))
      (node (ref "SPEAKER_SELECT") (pin "O") (pinfunction "O_O") (pintype "passive"))
    )
    (net (code "42") (name "Net-(IC1-+IN)") (class "Default")
      (node (ref "IC1") (pin "3") (pinfunction "+IN_3") (pintype "input"))
      (node (ref "R1") (pin "2") (pinfunction "2_2") (pintype "passive"))
    )
    (net (code "43") (name "Net-(IC1-GAIN-Pad1)") (class "Default")
      (node (ref "IC1") (pin "1") (pinfunction "GAIN_1") (pintype "passive"))
      (node (ref "R2") (pin "1") (pinfunction "1_1") (pintype "passive"))
    )
    (net (code "44") (name "Net-(IC1-OUT)") (class "Default")
      (node (ref "C3") (pin "+") (pinfunction "+_+") (pintype "passive"))
      (node (ref "IC1") (pin "5") (pinfunction "OUT_5") (pintype "output"))
      (node (ref "R3") (pin "1") (pinfunction "1_1") (pintype "passive"))
    )
    (net (code "45") (name "Net-(IC2B-+IN)") (class "Default")
      (node (ref "C47") (pin "2") (pinfunction "2_2") (pintype "passive"))
      (node (ref "IC2") (pin "5") (pinfunction "+IN_5") (pintype "input"))
      (node (ref "R54") (pin "1") (pinfunction "1_1") (pintype "passive"))
      (node (ref "R55") (pin "2") (pinfunction "2_2") (pintype "passive"))
    )
    (net (code "46") (name "Net-(IC2B--IN)") (class "Default")
      (node (ref "IC2") (pin "6") (pinfunction "-IN_6") (pintype "input"))
      (node (ref "IC2") (pin "7") (pinfunction "OUT_7") (pintype "output"))
      (node (ref "RA") (pin "2") (pinfunction "2_2") (pintype "passive"))
    )
    (net (code "47") (name "Net-(LED1-PadA)") (class "Default")
      (node (ref "LED1") (pin "A") (pinfunction "A_A") (pintype "passive"))
      (node (ref "LED101") (pin "A") (pinfunction "A_A") (pintype "passive"))
      (node (ref "LED11") (pin "A") (pinfunction "A_A") (pintype "passive"))
      (node (ref "LED111") (pin "A") (pinfunction "A_A") (pintype "passive"))
      (node (ref "LED121") (pin "A") (pinfunction "A_A") (pintype "passive"))
      (node (ref "LED131") (pin "A") (pinfunction "A_A") (pintype "passive"))
      (node (ref "LED141") (pin "A") (pinfunction "A_A") (pintype "passive"))
      (node (ref "LED21") (pin "A") (pinfunction "A_A") (pintype "passive"))
      (node (ref "LED31") (pin "A") (pinfunction "A_A") (pintype "passive"))
      (node (ref "LED41") (pin "A") (pinfunction "A_A") (pintype "passive"))
      (node (ref "LED51") (pin "A") (pinfunction "A_A") (pintype "passive"))
      (node (ref "LED61") (pin "A") (pinfunction "A_A") (pintype "passive"))
      (node (ref "LED71") (pin "A") (pinfunction "A_A") (pintype "passive"))
      (node (ref "LED81") (pin "A") (pinfunction "A_A") (pintype "passive"))
      (node (ref "LED91") (pin "A") (pinfunction "A_A") (pintype "passive"))
      (node (ref "T1") (pin "C") (pinfunction "C_C") (pintype "passive"))
    )
    (net (code "48") (name "Net-(LED1-PadC)") (class "Default")
      (node (ref "LED1") (pin "C") (pinfunction "C_C") (pintype "passive"))
      (node (ref "LED10") (pin "C") (pinfunction "C_C") (pintype "passive"))
      (node (ref "LED2") (pin "C") (pinfunction "C_C") (pintype "passive"))
      (node (ref "LED3") (pin "C") (pinfunction "C_C") (pintype "passive"))
      (node (ref "LED4") (pin "C") (pinfunction "C_C") (pintype "passive"))
      (node (ref "LED5") (pin "C") (pinfunction "C_C") (pintype "passive"))
      (node (ref "LED6") (pin "C") (pinfunction "C_C") (pintype "passive"))
      (node (ref "LED7") (pin "C") (pinfunction "C_C") (pintype "passive"))
      (node (ref "LED8") (pin "C") (pinfunction "C_C") (pintype "passive"))
      (node (ref "LED9") (pin "C") (pinfunction "C_C") (pintype "passive"))
      (node (ref "R5") (pin "2") (pinfunction "2_2") (pintype "passive"))
    )
    (net (code "49") (name "Net-(LED10-PadA)") (class "Default")
      (node (ref "LED10") (pin "A") (pinfunction "A_A") (pintype "passive"))
      (node (ref "LED100") (pin "A") (pinfunction "A_A") (pintype "passive"))
      (node (ref "LED110") (pin "A") (pinfunction "A_A") (pintype "passive"))
      (node (ref "LED120") (pin "A") (pinfunction "A_A") (pintype "passive"))
      (node (ref "LED130") (pin "A") (pinfunction "A_A") (pintype "passive"))
      (node (ref "LED140") (pin "A") (pinfunction "A_A") (pintype "passive"))
      (node (ref "LED150") (pin "A") (pinfunction "A_A") (pintype "passive"))
      (node (ref "LED20") (pin "A") (pinfunction "A_A") (pintype "passive"))
      (node (ref "LED30") (pin "A") (pinfunction "A_A") (pintype "passive"))
      (node (ref "LED40") (pin "A") (pinfunction "A_A") (pintype "passive"))
      (node (ref "LED50") (pin "A") (pinfunction "A_A") (pintype "passive"))
      (node (ref "LED60") (pin "A") (pinfunction "A_A") (pintype "passive"))
      (node (ref "LED70") (pin "A") (pinfunction "A_A") (pintype "passive"))
      (node (ref "LED80") (pin "A") (pinfunction "A_A") (pintype "passive"))
      (node (ref "LED90") (pin "A") (pinfunction "A_A") (pintype "passive"))
      (node (ref "T10") (pin "C") (pinfunction "C_C") (pintype "passive"))
    )
    (net (code "50") (name "Net-(LED11-PadC)") (class "Default")
      (node (ref "LED11") (pin "C") (pinfunction "C_C") (pintype "passive"))
      (node (ref "LED12") (pin "C") (pinfunction "C_C") (pintype "passive"))
      (node (ref "LED13") (pin "C") (pinfunction "C_C") (pintype "passive"))
      (node (ref "LED14") (pin "C") (pinfunction "C_C") (pintype "passive"))
      (node (ref "LED15") (pin "C") (pinfunction "C_C") (pintype "passive"))
      (node (ref "LED16") (pin "C") (pinfunction "C_C") (pintype "passive"))
      (node (ref "LED17") (pin "C") (pinfunction "C_C") (pintype "passive"))
      (node (ref "LED18") (pin "C") (pinfunction "C_C") (pintype "passive"))
      (node (ref "LED19") (pin "C") (pinfunction "C_C") (pintype "passive"))
      (node (ref "LED20") (pin "C") (pinfunction "C_C") (pintype "passive"))
      (node (ref "R6") (pin "2") (pinfunction "2_2") (pintype "passive"))
    )
    (net (code "51") (name "Net-(LED21-PadC)") (class "Default")
      (node (ref "LED21") (pin "C") (pinfunction "C_C") (pintype "passive"))
      (node (ref "LED22") (pin "C") (pinfunction "C_C") (pintype "passive"))
      (node (ref "LED23") (pin "C") (pinfunction "C_C") (pintype "passive"))
      (node (ref "LED24") (pin "C") (pinfunction "C_C") (pintype "passive"))
      (node (ref "LED25") (pin "C") (pinfunction "C_C") (pintype "passive"))
      (node (ref "LED26") (pin "C") (pinfunction "C_C") (pintype "passive"))
      (node (ref "LED27") (pin "C") (pinfunction "C_C") (pintype "passive"))
      (node (ref "LED28") (pin "C") (pinfunction "C_C") (pintype "passive"))
      (node (ref "LED29") (pin "C") (pinfunction "C_C") (pintype "passive"))
      (node (ref "LED30") (pin "C") (pinfunction "C_C") (pintype "passive"))
      (node (ref "R7") (pin "2") (pinfunction "2_2") (pintype "passive"))
    )
    (net (code "52") (name "Net-(LED31-PadC)") (class "Default")
      (node (ref "LED31") (pin "C") (pinfunction "C_C") (pintype "passive"))
      (node (ref "LED32") (pin "C") (pinfunction "C_C") (pintype "passive"))
      (node (ref "LED33") (pin "C") (pinfunction "C_C") (pintype "passive"))
      (node (ref "LED34") (pin "C") (pinfunction "C_C") (pintype "passive"))
      (node (ref "LED35") (pin "C") (pinfunction "C_C") (pintype "passive"))
      (node (ref "LED36") (pin "C") (pinfunction "C_C") (pintype "passive"))
      (node (ref "LED37") (pin "C") (pinfunction "C_C") (pintype "passive"))
      (node (ref "LED38") (pin "C") (pinfunction "C_C") (pintype "passive"))
      (node (ref "LED39") (pin "C") (pinfunction "C_C") (pintype "passive"))
      (node (ref "LED40") (pin "C") (pinfunction "C_C") (pintype "passive"))
      (node (ref "R8") (pin "2") (pinfunction "2_2") (pintype "passive"))
    )
    (net (code "53") (name "Net-(LED41-PadC)") (class "Default")
      (node (ref "LED41") (pin "C") (pinfunction "C_C") (pintype "passive"))
      (node (ref "LED42") (pin "C") (pinfunction "C_C") (pintype "passive"))
      (node (ref "LED43") (pin "C") (pinfunction "C_C") (pintype "passive"))
      (node (ref "LED44") (pin "C") (pinfunction "C_C") (pintype "passive"))
      (node (ref "LED45") (pin "C") (pinfunction "C_C") (pintype "passive"))
      (node (ref "LED46") (pin "C") (pinfunction "C_C") (pintype "passive"))
      (node (ref "LED47") (pin "C") (pinfunction "C_C") (pintype "passive"))
      (node (ref "LED48") (pin "C") (pinfunction "C_C") (pintype "passive"))
      (node (ref "LED49") (pin "C") (pinfunction "C_C") (pintype "passive"))
      (node (ref "LED50") (pin "C") (pinfunction "C_C") (pintype "passive"))
      (node (ref "R9") (pin "2") (pinfunction "2_2") (pintype "passive"))
    )
    (net (code "54") (name "Net-(LED51-PadC)") (class "Default")
      (node (ref "LED51") (pin "C") (pinfunction "C_C") (pintype "passive"))
      (node (ref "LED52") (pin "C") (pinfunction "C_C") (pintype "passive"))
      (node (ref "LED53") (pin "C") (pinfunction "C_C") (pintype "passive"))
      (node (ref "LED54") (pin "C") (pinfunction "C_C") (pintype "passive"))
      (node (ref "LED55") (pin "C") (pinfunction "C_C") (pintype "passive"))
      (node (ref "LED56") (pin "C") (pinfunction "C_C") (pintype "passive"))
      (node (ref "LED57") (pin "C") (pinfunction "C_C") (pintype "passive"))
      (node (ref "LED58") (pin "C") (pinfunction "C_C") (pintype "passive"))
      (node (ref "LED59") (pin "C") (pinfunction "C_C") (pintype "passive"))
      (node (ref "LED60") (pin "C") (pinfunction "C_C") (pintype "passive"))
      (node (ref "R10") (pin "2") (pinfunction "2_2") (pintype "passive"))
    )
    (net (code "55") (name "Net-(LED61-PadC)") (class "Default")
      (node (ref "LED61") (pin "C") (pinfunction "C_C") (pintype "passive"))
      (node (ref "LED62") (pin "C") (pinfunction "C_C") (pintype "passive"))
      (node (ref "LED63") (pin "C") (pinfunction "C_C") (pintype "passive"))
      (node (ref "LED64") (pin "C") (pinfunction "C_C") (pintype "passive"))
      (node (ref "LED65") (pin "C") (pinfunction "C_C") (pintype "passive"))
      (node (ref "LED66") (pin "C") (pinfunction "C_C") (pintype "passive"))
      (node (ref "LED67") (pin "C") (pinfunction "C_C") (pintype "passive"))
      (node (ref "LED68") (pin "C") (pinfunction "C_C") (pintype "passive"))
      (node (ref "LED69") (pin "C") (pinfunction "C_C") (pintype "passive"))
      (node (ref "LED70") (pin "C") (pinfunction "C_C") (pintype "passive"))
      (node (ref "R11") (pin "2") (pinfunction "2_2") (pintype "passive"))
    )
    (net (code "56") (name "Net-(LED71-PadC)") (class "Default")
      (node (ref "LED71") (pin "C") (pinfunction "C_C") (pintype "passive"))
      (node (ref "LED72") (pin "C") (pinfunction "C_C") (pintype "passive"))
      (node (ref "LED73") (pin "C") (pinfunction "C_C") (pintype "passive"))
      (node (ref "LED74") (pin "C") (pinfunction "C_C") (pintype "passive"))
      (node (ref "LED75") (pin "C") (pinfunction "C_C") (pintype "passive"))
      (node (ref "LED76") (pin "C") (pinfunction "C_C") (pintype "passive"))
      (node (ref "LED77") (pin "C") (pinfunction "C_C") (pintype "passive"))
      (node (ref "LED78") (pin "C") (pinfunction "C_C") (pintype "passive"))
      (node (ref "LED79") (pin "C") (pinfunction "C_C") (pintype "passive"))
      (node (ref "LED80") (pin "C") (pinfunction "C_C") (pintype "passive"))
      (node (ref "R12") (pin "2") (pinfunction "2_2") (pintype "passive"))
    )
    (net (code "57") (name "Net-(LED81-PadC)") (class "Default")
      (node (ref "LED81") (pin "C") (pinfunction "C_C") (pintype "passive"))
      (node (ref "LED82") (pin "C") (pinfunction "C_C") (pintype "passive"))
      (node (ref "LED83") (pin "C") (pinfunction "C_C") (pintype "passive"))
      (node (ref "LED84") (pin "C") (pinfunction "C_C") (pintype "passive"))
      (node (ref "LED85") (pin "C") (pinfunction "C_C") (pintype "passive"))
      (node (ref "LED86") (pin "C") (pinfunction "C_C") (pintype "passive"))
      (node (ref "LED87") (pin "C") (pinfunction "C_C") (pintype "passive"))
      (node (ref "LED88") (pin "C") (pinfunction "C_C") (pintype "passive"))
      (node (ref "LED89") (pin "C") (pinfunction "C_C") (pintype "passive"))
      (node (ref "LED90") (pin "C") (pinfunction "C_C") (pintype "passive"))
      (node (ref "R13") (pin "2") (pinfunction "2_2") (pintype "passive"))
    )
    (net (code "58") (name "Net-(LED100-PadC)") (class "Default")
      (node (ref "LED100") (pin "C") (pinfunction "C_C") (pintype "passive"))
      (node (ref "LED91") (pin "C") (pinfunction "C_C") (pintype "passive"))
      (node (ref "LED92") (pin "C") (pinfunction "C_C") (pintype "passive"))
      (node (ref "LED93") (pin "C") (pinfunction "C_C") (pintype "passive"))
      (node (ref "LED94") (pin "C") (pinfunction "C_C") (pintype "passive"))
      (node (ref "LED95") (pin "C") (pinfunction "C_C") (pintype "passive"))
      (node (ref "LED96") (pin "C") (pinfunction "C_C") (pintype "passive"))
      (node (ref "LED97") (pin "C") (pinfunction "C_C") (pintype "passive"))
      (node (ref "LED98") (pin "C") (pinfunction "C_C") (pintype "passive"))
      (node (ref "LED99") (pin "C") (pinfunction "C_C") (pintype "passive"))
      (node (ref "R14") (pin "2") (pinfunction "2_2") (pintype "passive"))
    )
    (net (code "59") (name "Net-(LED101-PadC)") (class "Default")
      (node (ref "LED101") (pin "C") (pinfunction "C_C") (pintype "passive"))
      (node (ref "LED102") (pin "C") (pinfunction "C_C") (pintype "passive"))
      (node (ref "LED103") (pin "C") (pinfunction "C_C") (pintype "passive"))
      (node (ref "LED104") (pin "C") (pinfunction "C_C") (pintype "passive"))
      (node (ref "LED105") (pin "C") (pinfunction "C_C") (pintype "passive"))
      (node (ref "LED106") (pin "C") (pinfunction "C_C") (pintype "passive"))
      (node (ref "LED107") (pin "C") (pinfunction "C_C") (pintype "passive"))
      (node (ref "LED108") (pin "C") (pinfunction "C_C") (pintype "passive"))
      (node (ref "LED109") (pin "C") (pinfunction "C_C") (pintype "passive"))
      (node (ref "LED110") (pin "C") (pinfunction "C_C") (pintype "passive"))
      (node (ref "R15") (pin "2") (pinfunction "2_2") (pintype "passive"))
    )
    (net (code "60") (name "Net-(LED102-PadA)") (class "Default")
      (node (ref "LED102") (pin "A") (pinfunction "A_A") (pintype "passive"))
      (node (ref "LED112") (pin "A") (pinfunction "A_A") (pintype "passive"))
      (node (ref "LED12") (pin "A") (pinfunction "A_A") (pintype "passive"))
      (node (ref "LED122") (pin "A") (pinfunction "A_A") (pintype "passive"))
      (node (ref "LED132") (pin "A") (pinfunction "A_A") (pintype "passive"))
      (node (ref "LED142") (pin "A") (pinfunction "A_A") (pintype "passive"))
      (node (ref "LED2") (pin "A") (pinfunction "A_A") (pintype "passive"))
      (node (ref "LED22") (pin "A") (pinfunction "A_A") (pintype "passive"))
      (node (ref "LED32") (pin "A") (pinfunction "A_A") (pintype "passive"))
      (node (ref "LED42") (pin "A") (pinfunction "A_A") (pintype "passive"))
      (node (ref "LED52") (pin "A") (pinfunction "A_A") (pintype "passive"))
      (node (ref "LED62") (pin "A") (pinfunction "A_A") (pintype "passive"))
      (node (ref "LED72") (pin "A") (pinfunction "A_A") (pintype "passive"))
      (node (ref "LED82") (pin "A") (pinfunction "A_A") (pintype "passive"))
      (node (ref "LED92") (pin "A") (pinfunction "A_A") (pintype "passive"))
      (node (ref "T2") (pin "C") (pinfunction "C_C") (pintype "passive"))
    )
    (net (code "61") (name "Net-(LED103-PadA)") (class "Default")
      (node (ref "LED103") (pin "A") (pinfunction "A_A") (pintype "passive"))
      (node (ref "LED113") (pin "A") (pinfunction "A_A") (pintype "passive"))
      (node (ref "LED123") (pin "A") (pinfunction "A_A") (pintype "passive"))
      (node (ref "LED13") (pin "A") (pinfunction "A_A") (pintype "passive"))
      (node (ref "LED133") (pin "A") (pinfunction "A_A") (pintype "passive"))
      (node (ref "LED143") (pin "A") (pinfunction "A_A") (pintype "passive"))
      (node (ref "LED23") (pin "A") (pinfunction "A_A") (pintype "passive"))
      (node (ref "LED3") (pin "A") (pinfunction "A_A") (pintype "passive"))
      (node (ref "LED33") (pin "A") (pinfunction "A_A") (pintype "passive"))
      (node (ref "LED43") (pin "A") (pinfunction "A_A") (pintype "passive"))
      (node (ref "LED53") (pin "A") (pinfunction "A_A") (pintype "passive"))
      (node (ref "LED63") (pin "A") (pinfunction "A_A") (pintype "passive"))
      (node (ref "LED73") (pin "A") (pinfunction "A_A") (pintype "passive"))
      (node (ref "LED83") (pin "A") (pinfunction "A_A") (pintype "passive"))
      (node (ref "LED93") (pin "A") (pinfunction "A_A") (pintype "passive"))
      (node (ref "T3") (pin "C") (pinfunction "C_C") (pintype "passive"))
    )
    (net (code "62") (name "Net-(LED104-PadA)") (class "Default")
      (node (ref "LED104") (pin "A") (pinfunction "A_A") (pintype "passive"))
      (node (ref "LED114") (pin "A") (pinfunction "A_A") (pintype "passive"))
      (node (ref "LED124") (pin "A") (pinfunction "A_A") (pintype "passive"))
      (node (ref "LED134") (pin "A") (pinfunction "A_A") (pintype "passive"))
      (node (ref "LED14") (pin "A") (pinfunction "A_A") (pintype "passive"))
      (node (ref "LED144") (pin "A") (pinfunction "A_A") (pintype "passive"))
      (node (ref "LED24") (pin "A") (pinfunction "A_A") (pintype "passive"))
      (node (ref "LED34") (pin "A") (pinfunction "A_A") (pintype "passive"))
      (node (ref "LED4") (pin "A") (pinfunction "A_A") (pintype "passive"))
      (node (ref "LED44") (pin "A") (pinfunction "A_A") (pintype "passive"))
      (node (ref "LED54") (pin "A") (pinfunction "A_A") (pintype "passive"))
      (node (ref "LED64") (pin "A") (pinfunction "A_A") (pintype "passive"))
      (node (ref "LED74") (pin "A") (pinfunction "A_A") (pintype "passive"))
      (node (ref "LED84") (pin "A") (pinfunction "A_A") (pintype "passive"))
      (node (ref "LED94") (pin "A") (pinfunction "A_A") (pintype "passive"))
      (node (ref "T4") (pin "C") (pinfunction "C_C") (pintype "passive"))
    )
    (net (code "63") (name "Net-(LED105-PadA)") (class "Default")
      (node (ref "LED105") (pin "A") (pinfunction "A_A") (pintype "passive"))
      (node (ref "LED115") (pin "A") (pinfunction "A_A") (pintype "passive"))
      (node (ref "LED125") (pin "A") (pinfunction "A_A") (pintype "passive"))
      (node (ref "LED135") (pin "A") (pinfunction "A_A") (pintype "passive"))
      (node (ref "LED145") (pin "A") (pinfunction "A_A") (pintype "passive"))
      (node (ref "LED15") (pin "A") (pinfunction "A_A") (pintype "passive"))
      (node (ref "LED25") (pin "A") (pinfunction "A_A") (pintype "passive"))
      (node (ref "LED35") (pin "A") (pinfunction "A_A") (pintype "passive"))
      (node (ref "LED45") (pin "A") (pinfunction "A_A") (pintype "passive"))
      (node (ref "LED5") (pin "A") (pinfunction "A_A") (pintype "passive"))
      (node (ref "LED55") (pin "A") (pinfunction "A_A") (pintype "passive"))
      (node (ref "LED65") (pin "A") (pinfunction "A_A") (pintype "passive"))
      (node (ref "LED75") (pin "A") (pinfunction "A_A") (pintype "passive"))
      (node (ref "LED85") (pin "A") (pinfunction "A_A") (pintype "passive"))
      (node (ref "LED95") (pin "A") (pinfunction "A_A") (pintype "passive"))
      (node (ref "T5") (pin "C") (pinfunction "C_C") (pintype "passive"))
    )
    (net (code "64") (name "Net-(LED106-PadA)") (class "Default")
      (node (ref "LED106") (pin "A") (pinfunction "A_A") (pintype "passive"))
      (node (ref "LED116") (pin "A") (pinfunction "A_A") (pintype "passive"))
      (node (ref "LED126") (pin "A") (pinfunction "A_A") (pintype "passive"))
      (node (ref "LED136") (pin "A") (pinfunction "A_A") (pintype "passive"))
      (node (ref "LED146") (pin "A") (pinfunction "A_A") (pintype "passive"))
      (node (ref "LED16") (pin "A") (pinfunction "A_A") (pintype "passive"))
      (node (ref "LED26") (pin "A") (pinfunction "A_A") (pintype "passive"))
      (node (ref "LED36") (pin "A") (pinfunction "A_A") (pintype "passive"))
      (node (ref "LED46") (pin "A") (pinfunction "A_A") (pintype "passive"))
      (node (ref "LED56") (pin "A") (pinfunction "A_A") (pintype "passive"))
      (node (ref "LED6") (pin "A") (pinfunction "A_A") (pintype "passive"))
      (node (ref "LED66") (pin "A") (pinfunction "A_A") (pintype "passive"))
      (node (ref "LED76") (pin "A") (pinfunction "A_A") (pintype "passive"))
      (node (ref "LED86") (pin "A") (pinfunction "A_A") (pintype "passive"))
      (node (ref "LED96") (pin "A") (pinfunction "A_A") (pintype "passive"))
      (node (ref "T6") (pin "C") (pinfunction "C_C") (pintype "passive"))
    )
    (net (code "65") (name "Net-(LED107-PadA)") (class "Default")
      (node (ref "LED107") (pin "A") (pinfunction "A_A") (pintype "passive"))
      (node (ref "LED117") (pin "A") (pinfunction "A_A") (pintype "passive"))
      (node (ref "LED127") (pin "A") (pinfunction "A_A") (pintype "passive"))
      (node (ref "LED137") (pin "A") (pinfunction "A_A") (pintype "passive"))
      (node (ref "LED147") (pin "A") (pinfunction "A_A") (pintype "passive"))
      (node (ref "LED17") (pin "A") (pinfunction "A_A") (pintype "passive"))
      (node (ref "LED27") (pin "A") (pinfunction "A_A") (pintype "passive"))
      (node (ref "LED37") (pin "A") (pinfunction "A_A") (pintype "passive"))
      (node (ref "LED47") (pin "A") (pinfunction "A_A") (pintype "passive"))
      (node (ref "LED57") (pin "A") (pinfunction "A_A") (pintype "passive"))
      (node (ref "LED67") (pin "A") (pinfunction "A_A") (pintype "passive"))
      (node (ref "LED7") (pin "A") (pinfunction "A_A") (pintype "passive"))
      (node (ref "LED77") (pin "A") (pinfunction "A_A") (pintype "passive"))
      (node (ref "LED87") (pin "A") (pinfunction "A_A") (pintype "passive"))
      (node (ref "LED97") (pin "A") (pinfunction "A_A") (pintype "passive"))
      (node (ref "T7") (pin "C") (pinfunction "C_C") (pintype "passive"))
    )
    (net (code "66") (name "Net-(LED108-PadA)") (class "Default")
      (node (ref "LED108") (pin "A") (pinfunction "A_A") (pintype "passive"))
      (node (ref "LED118") (pin "A") (pinfunction "A_A") (pintype "passive"))
      (node (ref "LED128") (pin "A") (pinfunction "A_A") (pintype "passive"))
      (node (ref "LED138") (pin "A") (pinfunction "A_A") (pintype "passive"))
      (node (ref "LED148") (pin "A") (pinfunction "A_A") (pintype "passive"))
      (node (ref "LED18") (pin "A") (pinfunction "A_A") (pintype "passive"))
      (node (ref "LED28") (pin "A") (pinfunction "A_A") (pintype "passive"))
      (node (ref "LED38") (pin "A") (pinfunction "A_A") (pintype "passive"))
      (node (ref "LED48") (pin "A") (pinfunction "A_A") (pintype "passive"))
      (node (ref "LED58") (pin "A") (pinfunction "A_A") (pintype "passive"))
      (node (ref "LED68") (pin "A") (pinfunction "A_A") (pintype "passive"))
      (node (ref "LED78") (pin "A") (pinfunction "A_A") (pintype "passive"))
      (node (ref "LED8") (pin "A") (pinfunction "A_A") (pintype "passive"))
      (node (ref "LED88") (pin "A") (pinfunction "A_A") (pintype "passive"))
      (node (ref "LED98") (pin "A") (pinfunction "A_A") (pintype "passive"))
      (node (ref "T8") (pin "C") (pinfunction "C_C") (pintype "passive"))
    )
    (net (code "67") (name "Net-(LED109-PadA)") (class "Default")
      (node (ref "LED109") (pin "A") (pinfunction "A_A") (pintype "passive"))
      (node (ref "LED119") (pin "A") (pinfunction "A_A") (pintype "passive"))
      (node (ref "LED129") (pin "A") (pinfunction "A_A") (pintype "passive"))
      (node (ref "LED139") (pin "A") (pinfunction "A_A") (pintype "passive"))
      (node (ref "LED149") (pin "A") (pinfunction "A_A") (pintype "passive"))
      (node (ref "LED19") (pin "A") (pinfunction "A_A") (pintype "passive"))
      (node (ref "LED29") (pin "A") (pinfunction "A_A") (pintype "passive"))
      (node (ref "LED39") (pin "A") (pinfunction "A_A") (pintype "passive"))
      (node (ref "LED49") (pin "A") (pinfunction "A_A") (pintype "passive"))
      (node (ref "LED59") (pin "A") (pinfunction "A_A") (pintype "passive"))
      (node (ref "LED69") (pin "A") (pinfunction "A_A") (pintype "passive"))
      (node (ref "LED79") (pin "A") (pinfunction "A_A") (pintype "passive"))
      (node (ref "LED89") (pin "A") (pinfunction "A_A") (pintype "passive"))
      (node (ref "LED9") (pin "A") (pinfunction "A_A") (pintype "passive"))
      (node (ref "LED99") (pin "A") (pinfunction "A_A") (pintype "passive"))
      (node (ref "T9") (pin "C") (pinfunction "C_C") (pintype "passive"))
    )
    (net (code "68") (name "Net-(LED111-PadC)") (class "Default")
      (node (ref "LED111") (pin "C") (pinfunction "C_C") (pintype "passive"))
      (node (ref "LED112") (pin "C") (pinfunction "C_C") (pintype "passive"))
      (node (ref "LED113") (pin "C") (pinfunction "C_C") (pintype "passive"))
      (node (ref "LED114") (pin "C") (pinfunction "C_C") (pintype "passive"))
      (node (ref "LED115") (pin "C") (pinfunction "C_C") (pintype "passive"))
      (node (ref "LED116") (pin "C") (pinfunction "C_C") (pintype "passive"))
      (node (ref "LED117") (pin "C") (pinfunction "C_C") (pintype "passive"))
      (node (ref "LED118") (pin "C") (pinfunction "C_C") (pintype "passive"))
      (node (ref "LED119") (pin "C") (pinfunction "C_C") (pintype "passive"))
      (node (ref "LED120") (pin "C") (pinfunction "C_C") (pintype "passive"))
      (node (ref "R16") (pin "2") (pinfunction "2_2") (pintype "passive"))
    )
    (net (code "69") (name "Net-(LED121-PadC)") (class "Default")
      (node (ref "LED121") (pin "C") (pinfunction "C_C") (pintype "passive"))
      (node (ref "LED122") (pin "C") (pinfunction "C_C") (pintype "passive"))
      (node (ref "LED123") (pin "C") (pinfunction "C_C") (pintype "passive"))
      (node (ref "LED124") (pin "C") (pinfunction "C_C") (pintype "passive"))
      (node (ref "LED125") (pin "C") (pinfunction "C_C") (pintype "passive"))
      (node (ref "LED126") (pin "C") (pinfunction "C_C") (pintype "passive"))
      (node (ref "LED127") (pin "C") (pinfunction "C_C") (pintype "passive"))
      (node (ref "LED128") (pin "C") (pinfunction "C_C") (pintype "passive"))
      (node (ref "LED129") (pin "C") (pinfunction "C_C") (pintype "passive"))
      (node (ref "LED130") (pin "C") (pinfunction "C_C") (pintype "passive"))
      (node (ref "R17") (pin "2") (pinfunction "2_2") (pintype "passive"))
    )
    (net (code "70") (name "Net-(LED131-PadC)") (class "Default")
      (node (ref "LED131") (pin "C") (pinfunction "C_C") (pintype "passive"))
      (node (ref "LED132") (pin "C") (pinfunction "C_C") (pintype "passive"))
      (node (ref "LED133") (pin "C") (pinfunction "C_C") (pintype "passive"))
      (node (ref "LED134") (pin "C") (pinfunction "C_C") (pintype "passive"))
      (node (ref "LED135") (pin "C") (pinfunction "C_C") (pintype "passive"))
      (node (ref "LED136") (pin "C") (pinfunction "C_C") (pintype "passive"))
      (node (ref "LED137") (pin "C") (pinfunction "C_C") (pintype "passive"))
      (node (ref "LED138") (pin "C") (pinfunction "C_C") (pintype "passive"))
      (node (ref "LED139") (pin "C") (pinfunction "C_C") (pintype "passive"))
      (node (ref "LED140") (pin "C") (pinfunction "C_C") (pintype "passive"))
      (node (ref "R18") (pin "2") (pinfunction "2_2") (pintype "passive"))
    )
    (net (code "71") (name "Net-(LED141-PadC)") (class "Default")
      (node (ref "LED141") (pin "C") (pinfunction "C_C") (pintype "passive"))
      (node (ref "LED142") (pin "C") (pinfunction "C_C") (pintype "passive"))
      (node (ref "LED143") (pin "C") (pinfunction "C_C") (pintype "passive"))
      (node (ref "LED144") (pin "C") (pinfunction "C_C") (pintype "passive"))
      (node (ref "LED145") (pin "C") (pinfunction "C_C") (pintype "passive"))
      (node (ref "LED146") (pin "C") (pinfunction "C_C") (pintype "passive"))
      (node (ref "LED147") (pin "C") (pinfunction "C_C") (pintype "passive"))
      (node (ref "LED148") (pin "C") (pinfunction "C_C") (pintype "passive"))
      (node (ref "LED149") (pin "C") (pinfunction "C_C") (pintype "passive"))
      (node (ref "LED150") (pin "C") (pinfunction "C_C") (pintype "passive"))
      (node (ref "R19") (pin "2") (pinfunction "2_2") (pintype "passive"))
    )
    (net (code "72") (name "Net-(R4-Pad2)") (class "Default")
      (node (ref "R4") (pin "2") (pinfunction "2_2") (pintype "passive"))
      (node (ref "T1") (pin "B") (pinfunction "B_B") (pintype "passive"))
    )
    (net (code "73") (name "Net-(R20-Pad2)") (class "Default")
      (node (ref "R20") (pin "2") (pinfunction "2_2") (pintype "passive"))
      (node (ref "T2") (pin "B") (pinfunction "B_B") (pintype "passive"))
    )
    (net (code "74") (name "Net-(R21-Pad2)") (class "Default")
      (node (ref "R21") (pin "2") (pinfunction "2_2") (pintype "passive"))
      (node (ref "T3") (pin "B") (pinfunction "B_B") (pintype "passive"))
    )
    (net (code "75") (name "Net-(R22-Pad2)") (class "Default")
      (node (ref "R22") (pin "2") (pinfunction "2_2") (pintype "passive"))
      (node (ref "T4") (pin "B") (pinfunction "B_B") (pintype "passive"))
    )
    (net (code "76") (name "Net-(R23-Pad2)") (class "Default")
      (node (ref "R23") (pin "2") (pinfunction "2_2") (pintype "passive"))
      (node (ref "T5") (pin "B") (pinfunction "B_B") (pintype "passive"))
    )
    (net (code "77") (name "Net-(R24-Pad2)") (class "Default")
      (node (ref "R24") (pin "2") (pinfunction "2_2") (pintype "passive"))
      (node (ref "T6") (pin "B") (pinfunction "B_B") (pintype "passive"))
    )
    (net (code "78") (name "Net-(R25-Pad2)") (class "Default")
      (node (ref "R25") (pin "2") (pinfunction "2_2") (pintype "passive"))
      (node (ref "T7") (pin "B") (pinfunction "B_B") (pintype "passive"))
    )
    (net (code "79") (name "Net-(R26-Pad2)") (class "Default")
      (node (ref "R26") (pin "2") (pinfunction "2_2") (pintype "passive"))
      (node (ref "T8") (pin "B") (pinfunction "B_B") (pintype "passive"))
    )
    (net (code "80") (name "Net-(R27-Pad2)") (class "Default")
      (node (ref "R27") (pin "2") (pinfunction "2_2") (pintype "passive"))
      (node (ref "T9") (pin "B") (pinfunction "B_B") (pintype "passive"))
    )
    (net (code "81") (name "Net-(R28-Pad2)") (class "Default")
      (node (ref "R28") (pin "2") (pinfunction "2_2") (pintype "passive"))
      (node (ref "T10") (pin "B") (pinfunction "B_B") (pintype "passive"))
    )
    (net (code "82") (name "Net-(VOLUME-E)") (class "Default")
      (node (ref "C5") (pin "2") (pinfunction "2_2") (pintype "passive"))
      (node (ref "VOLUME") (pin "3") (pinfunction "E_3") (pintype "passive"))
    )
    (net (code "83") (name "Net-(VOLUME-S)") (class "Default")
      (node (ref "R1") (pin "1") (pinfunction "1_1") (pintype "passive"))
      (node (ref "VOLUME") (pin "2") (pinfunction "S_2") (pintype "passive"))
    )
    (net (code "84") (name "V+") (class "Default")
      (node (ref "C10") (pin "1") (pinfunction "1_1") (pintype "passive"))
      (node (ref "C2") (pin "+") (pinfunction "+_+") (pintype "passive"))
      (node (ref "C6") (pin "+") (pinfunction "+_+") (pintype "passive"))
      (node (ref "IC1") (pin "6") (pinfunction "VS_6") (pintype "power_in"))
      (node (ref "IC6") (pin "1") (pinfunction "VI_1") (pintype "input"))
      (node (ref "POWER_JACK") (pin "TIP") (pinfunction "TIP_TIP") (pintype "bidirectional"))
    )
    (net (code "85") (name "unconnected-(BD1-PadBOOT)") (class "Default")
      (node (ref "BD1") (pin "BOOT") (pinfunction "BOOT_BOOT") (pintype "bidirectional"))
    )
    (net (code "86") (name "unconnected-(BD1-PadGND3)") (class "Default")
      (node (ref "BD1") (pin "GND3") (pinfunction "GND3_GND3") (pintype "bidirectional"))
    )
    (net (code "87") (name "unconnected-(BD1-PadGND4)") (class "Default")
      (node (ref "BD1") (pin "GND4") (pinfunction "GND4_GND4") (pintype "bidirectional"))
    )
    (net (code "88") (name "unconnected-(BD1-PadNC)") (class "Default")
      (node (ref "BD1") (pin "NC") (pinfunction "NC_NC") (pintype "bidirectional"))
    )
    (net (code "89") (name "unconnected-(BD1-PadNRST)") (class "Default")
      (node (ref "BD1") (pin "NRST") (pinfunction "NRST_NRST") (pintype "bidirectional"))
    )
    (net (code "90") (name "unconnected-(BD1-PadPA4)") (class "Default")
      (node (ref "BD1") (pin "PA4") (pinfunction "PA4_PA4") (pintype "bidirectional"))
    )
    (net (code "91") (name "unconnected-(BD1-PadPA5)") (class "Default")
      (node (ref "BD1") (pin "PA5") (pinfunction "PA5_PA5") (pintype "bidirectional"))
    )
    (net (code "92") (name "unconnected-(BD1-PadPA6)") (class "Default")
      (node (ref "BD1") (pin "PA6") (pinfunction "PA6_PA6") (pintype "bidirectional"))
    )
    (net (code "93") (name "unconnected-(BD1-PadPA7)") (class "Default")
      (node (ref "BD1") (pin "PA7") (pinfunction "PA7_PA7") (pintype "bidirectional"))
    )
    (net (code "94") (name "unconnected-(BD1-PadPA8)") (class "Default")
      (node (ref "BD1") (pin "PA8") (pinfunction "PA8_PA8") (pintype "bidirectional"))
    )
    (net (code "95") (name "unconnected-(BD1-PadPA9)") (class "Default")
      (node (ref "BD1") (pin "PA9") (pinfunction "PA9_PA9") (pintype "bidirectional"))
    )
    (net (code "96") (name "unconnected-(BD1-PadPA10)") (class "Default")
      (node (ref "BD1") (pin "PA10") (pinfunction "PA10_PA10") (pintype "bidirectional"))
    )
    (net (code "97") (name "unconnected-(BD1-PadPA13)") (class "Default")
      (node (ref "BD1") (pin "PA13") (pinfunction "PA13_PA13") (pintype "bidirectional"))
    )
    (net (code "98") (name "unconnected-(BD1-PadPA14)") (class "Default")
      (node (ref "BD1") (pin "PA14") (pinfunction "PA14_PA14") (pintype "bidirectional"))
    )
    (net (code "99") (name "unconnected-(BD1-PadPA15)") (class "Default")
      (node (ref "BD1") (pin "PA15") (pinfunction "PA15_PA15") (pintype "bidirectional"))
    )
    (net (code "100") (name "unconnected-(BD1-PadPB0)") (class "Default")
      (node (ref "BD1") (pin "PB0") (pinfunction "PB0_PB0") (pintype "bidirectional"))
    )
    (net (code "101") (name "unconnected-(BD1-PadPB2)") (class "Default")
      (node (ref "BD1") (pin "PB2") (pinfunction "PB2_PB2") (pintype "bidirectional"))
    )
    (net (code "102") (name "unconnected-(BD1-PadPB6)") (class "Default")
      (node (ref "BD1") (pin "PB6") (pinfunction "PB6_PB6") (pintype "bidirectional"))
    )
    (net (code "103") (name "unconnected-(BD1-PadPB7)") (class "Default")
      (node (ref "BD1") (pin "PB7") (pinfunction "PB7_PB7") (pintype "bidirectional"))
    )
    (net (code "104") (name "unconnected-(BD1-PadPB8)") (class "Default")
      (node (ref "BD1") (pin "PB8") (pinfunction "PB8_PB8") (pintype "bidirectional"))
    )
    (net (code "105") (name "unconnected-(BD1-PadPB9)") (class "Default")
      (node (ref "BD1") (pin "PB9") (pinfunction "PB9_PB9") (pintype "bidirectional"))
    )
    (net (code "106") (name "unconnected-(BD1-PadPB10)") (class "Default")
      (node (ref "BD1") (pin "PB10") (pinfunction "PB10_PB10") (pintype "bidirectional"))
    )
    (net (code "107") (name "unconnected-(BD1-PadPB15)") (class "Default")
      (node (ref "BD1") (pin "PB15") (pinfunction "PB15_PB15") (pintype "bidirectional"))
    )
    (net (code "108") (name "unconnected-(BD1-PadPC0)") (class "Default")
      (node (ref "BD1") (pin "PC0") (pinfunction "PC0_PC0") (pintype "bidirectional"))
    )
    (net (code "109") (name "unconnected-(BD1-PadPC3)") (class "Default")
      (node (ref "BD1") (pin "PC3") (pinfunction "PC3_PC3") (pintype "bidirectional"))
    )
    (net (code "110") (name "unconnected-(BD1-PadPC6)") (class "Default")
      (node (ref "BD1") (pin "PC6") (pinfunction "PC6_PC6") (pintype "bidirectional"))
    )
    (net (code "111") (name "unconnected-(BD1-PadPC7)") (class "Default")
      (node (ref "BD1") (pin "PC7") (pinfunction "PC7_PC7") (pintype "bidirectional"))
    )
    (net (code "112") (name "unconnected-(BD1-PadPC8)") (class "Default")
      (node (ref "BD1") (pin "PC8") (pinfunction "PC8_PC8") (pintype "bidirectional"))
    )
    (net (code "113") (name "unconnected-(BD1-PadPC9)") (class "Default")
      (node (ref "BD1") (pin "PC9") (pinfunction "PC9_PC9") (pintype "bidirectional"))
    )
    (net (code "114") (name "unconnected-(BD1-PadPC10)") (class "Default")
      (node (ref "BD1") (pin "PC10") (pinfunction "PC10_PC10") (pintype "bidirectional"))
    )
    (net (code "115") (name "unconnected-(BD1-PadPC11)") (class "Default")
      (node (ref "BD1") (pin "PC11") (pinfunction "PC11_PC11") (pintype "bidirectional"))
    )
    (net (code "116") (name "unconnected-(BD1-PadPC12)") (class "Default")
      (node (ref "BD1") (pin "PC12") (pinfunction "PC12_PC12") (pintype "bidirectional"))
    )
    (net (code "117") (name "unconnected-(BD1-PadPC13)") (class "Default")
      (node (ref "BD1") (pin "PC13") (pinfunction "PC13_PC13") (pintype "bidirectional"))
    )
    (net (code "118") (name "unconnected-(BD1-PadPC14)") (class "Default")
      (node (ref "BD1") (pin "PC14") (pinfunction "PC14_PC14") (pintype "bidirectional"))
    )
    (net (code "119") (name "unconnected-(BD1-PadPC15)") (class "Default")
      (node (ref "BD1") (pin "PC15") (pinfunction "PC15_PC15") (pintype "bidirectional"))
    )
    (net (code "120") (name "unconnected-(BD1-PadPD0)") (class "Default")
      (node (ref "BD1") (pin "PD0") (pinfunction "PD0_PD0") (pintype "bidirectional"))
    )
    (net (code "121") (name "unconnected-(BD1-PadPD4)") (class "Default")
      (node (ref "BD1") (pin "PD4") (pinfunction "PD4_PD4") (pintype "bidirectional"))
    )
    (net (code "122") (name "unconnected-(BD1-PadPD5)") (class "Default")
      (node (ref "BD1") (pin "PD5") (pinfunction "PD5_PD5") (pintype "bidirectional"))
    )
    (net (code "123") (name "unconnected-(BD1-PadPD12)") (class "Default")
      (node (ref "BD1") (pin "PD12") (pinfunction "PD12_PD12") (pintype "bidirectional"))
    )
    (net (code "124") (name "unconnected-(BD1-PadPD13)") (class "Default")
      (node (ref "BD1") (pin "PD13") (pinfunction "PD13_PD13") (pintype "bidirectional"))
    )
    (net (code "125") (name "unconnected-(BD1-PadPD14)") (class "Default")
      (node (ref "BD1") (pin "PD14") (pinfunction "PD14_PD14") (pintype "bidirectional"))
    )
    (net (code "126") (name "unconnected-(BD1-PadPD15)") (class "Default")
      (node (ref "BD1") (pin "PD15") (pinfunction "PD15_PD15") (pintype "bidirectional"))
    )
    (net (code "127") (name "unconnected-(BD1-PadPE0)") (class "Default")
      (node (ref "BD1") (pin "PE0") (pinfunction "PE0_PE0") (pintype "bidirectional"))
    )
    (net (code "128") (name "unconnected-(BD1-PadPE1)") (class "Default")
      (node (ref "BD1") (pin "PE1") (pinfunction "PE1_PE1") (pintype "bidirectional"))
    )
    (net (code "129") (name "unconnected-(BD1-PadPE3)") (class "Default")
      (node (ref "BD1") (pin "PE3") (pinfunction "PE3_PE3") (pintype "bidirectional"))
    )
    (net (code "130") (name "unconnected-(BD1-PadPE7)") (class "Default")
      (node (ref "BD1") (pin "PE7") (pinfunction "PE7_PE7") (pintype "bidirectional"))
    )
    (net (code "131") (name "unconnected-(BD1-PadPE8)") (class "Default")
      (node (ref "BD1") (pin "PE8") (pinfunction "PE8_PE8") (pintype "bidirectional"))
    )
    (net (code "132") (name "unconnected-(BD1-PadPE9)") (class "Default")
      (node (ref "BD1") (pin "PE9") (pinfunction "PE9_PE9") (pintype "bidirectional"))
    )
    (net (code "133") (name "unconnected-(BD1-PadPE10)") (class "Default")
      (node (ref "BD1") (pin "PE10") (pinfunction "PE10_PE10") (pintype "bidirectional"))
    )
    (net (code "134") (name "unconnected-(BD1-PadPE11)") (class "Default")
      (node (ref "BD1") (pin "PE11") (pinfunction "PE11_PE11") (pintype "bidirectional"))
    )
    (net (code "135") (name "unconnected-(BD1-PadPE12)") (class "Default")
      (node (ref "BD1") (pin "PE12") (pinfunction "PE12_PE12") (pintype "bidirectional"))
    )
    (net (code "136") (name "unconnected-(BD1-PadPE14)") (class "Default")
      (node (ref "BD1") (pin "PE14") (pinfunction "PE14_PE14") (pintype "bidirectional"))
    )
    (net (code "137") (name "unconnected-(BD1-PadPH0)") (class "Default")
      (node (ref "BD1") (pin "PH0") (pinfunction "PH0_PH0") (pintype "bidirectional"))
    )
    (net (code "138") (name "unconnected-(BD1-PadPH1)") (class "Default")
      (node (ref "BD1") (pin "PH1") (pinfunction "PH1_PH1") (pintype "bidirectional"))
    )
    (net (code "139") (name "unconnected-(BD1-PadVDD)") (class "Default")
      (node (ref "BD1") (pin "VDD") (pinfunction "VDD_VDD") (pintype "bidirectional"))
    )
    (net (code "140") (name "unconnected-(BD1-PadVDD2)") (class "Default")
      (node (ref "BD1") (pin "VDD2") (pinfunction "VDD2_VDD2") (pintype "bidirectional"))
    )
    (net (code "141") (name "unconnected-(BD1-PadVDD3)") (class "Default")
      (node (ref "BD1") (pin "VDD3") (pinfunction "VDD3_VDD3") (pintype "bidirectional"))
    )
    (net (code "142") (name "unconnected-(IC1-BYPASS-Pad7)") (class "Default")
      (node (ref "IC1") (pin "7") (pinfunction "BYPASS_7") (pintype "passive"))
    )
    (net (code "143") (name "unconnected-(U$1-Pad1)") (class "Default")
      (node (ref "U$1") (pin "1") (pinfunction "1_1") (pintype "passive"))
    )
    (net (code "144") (name "unconnected-(U$1-Pad2)") (class "Default")
      (node (ref "U$1") (pin "2") (pinfunction "2_2") (pintype "passive"))
    )
  )
)
